# JKW_standalone.net
KiCad netlist of a schematic drawn in EAGLE
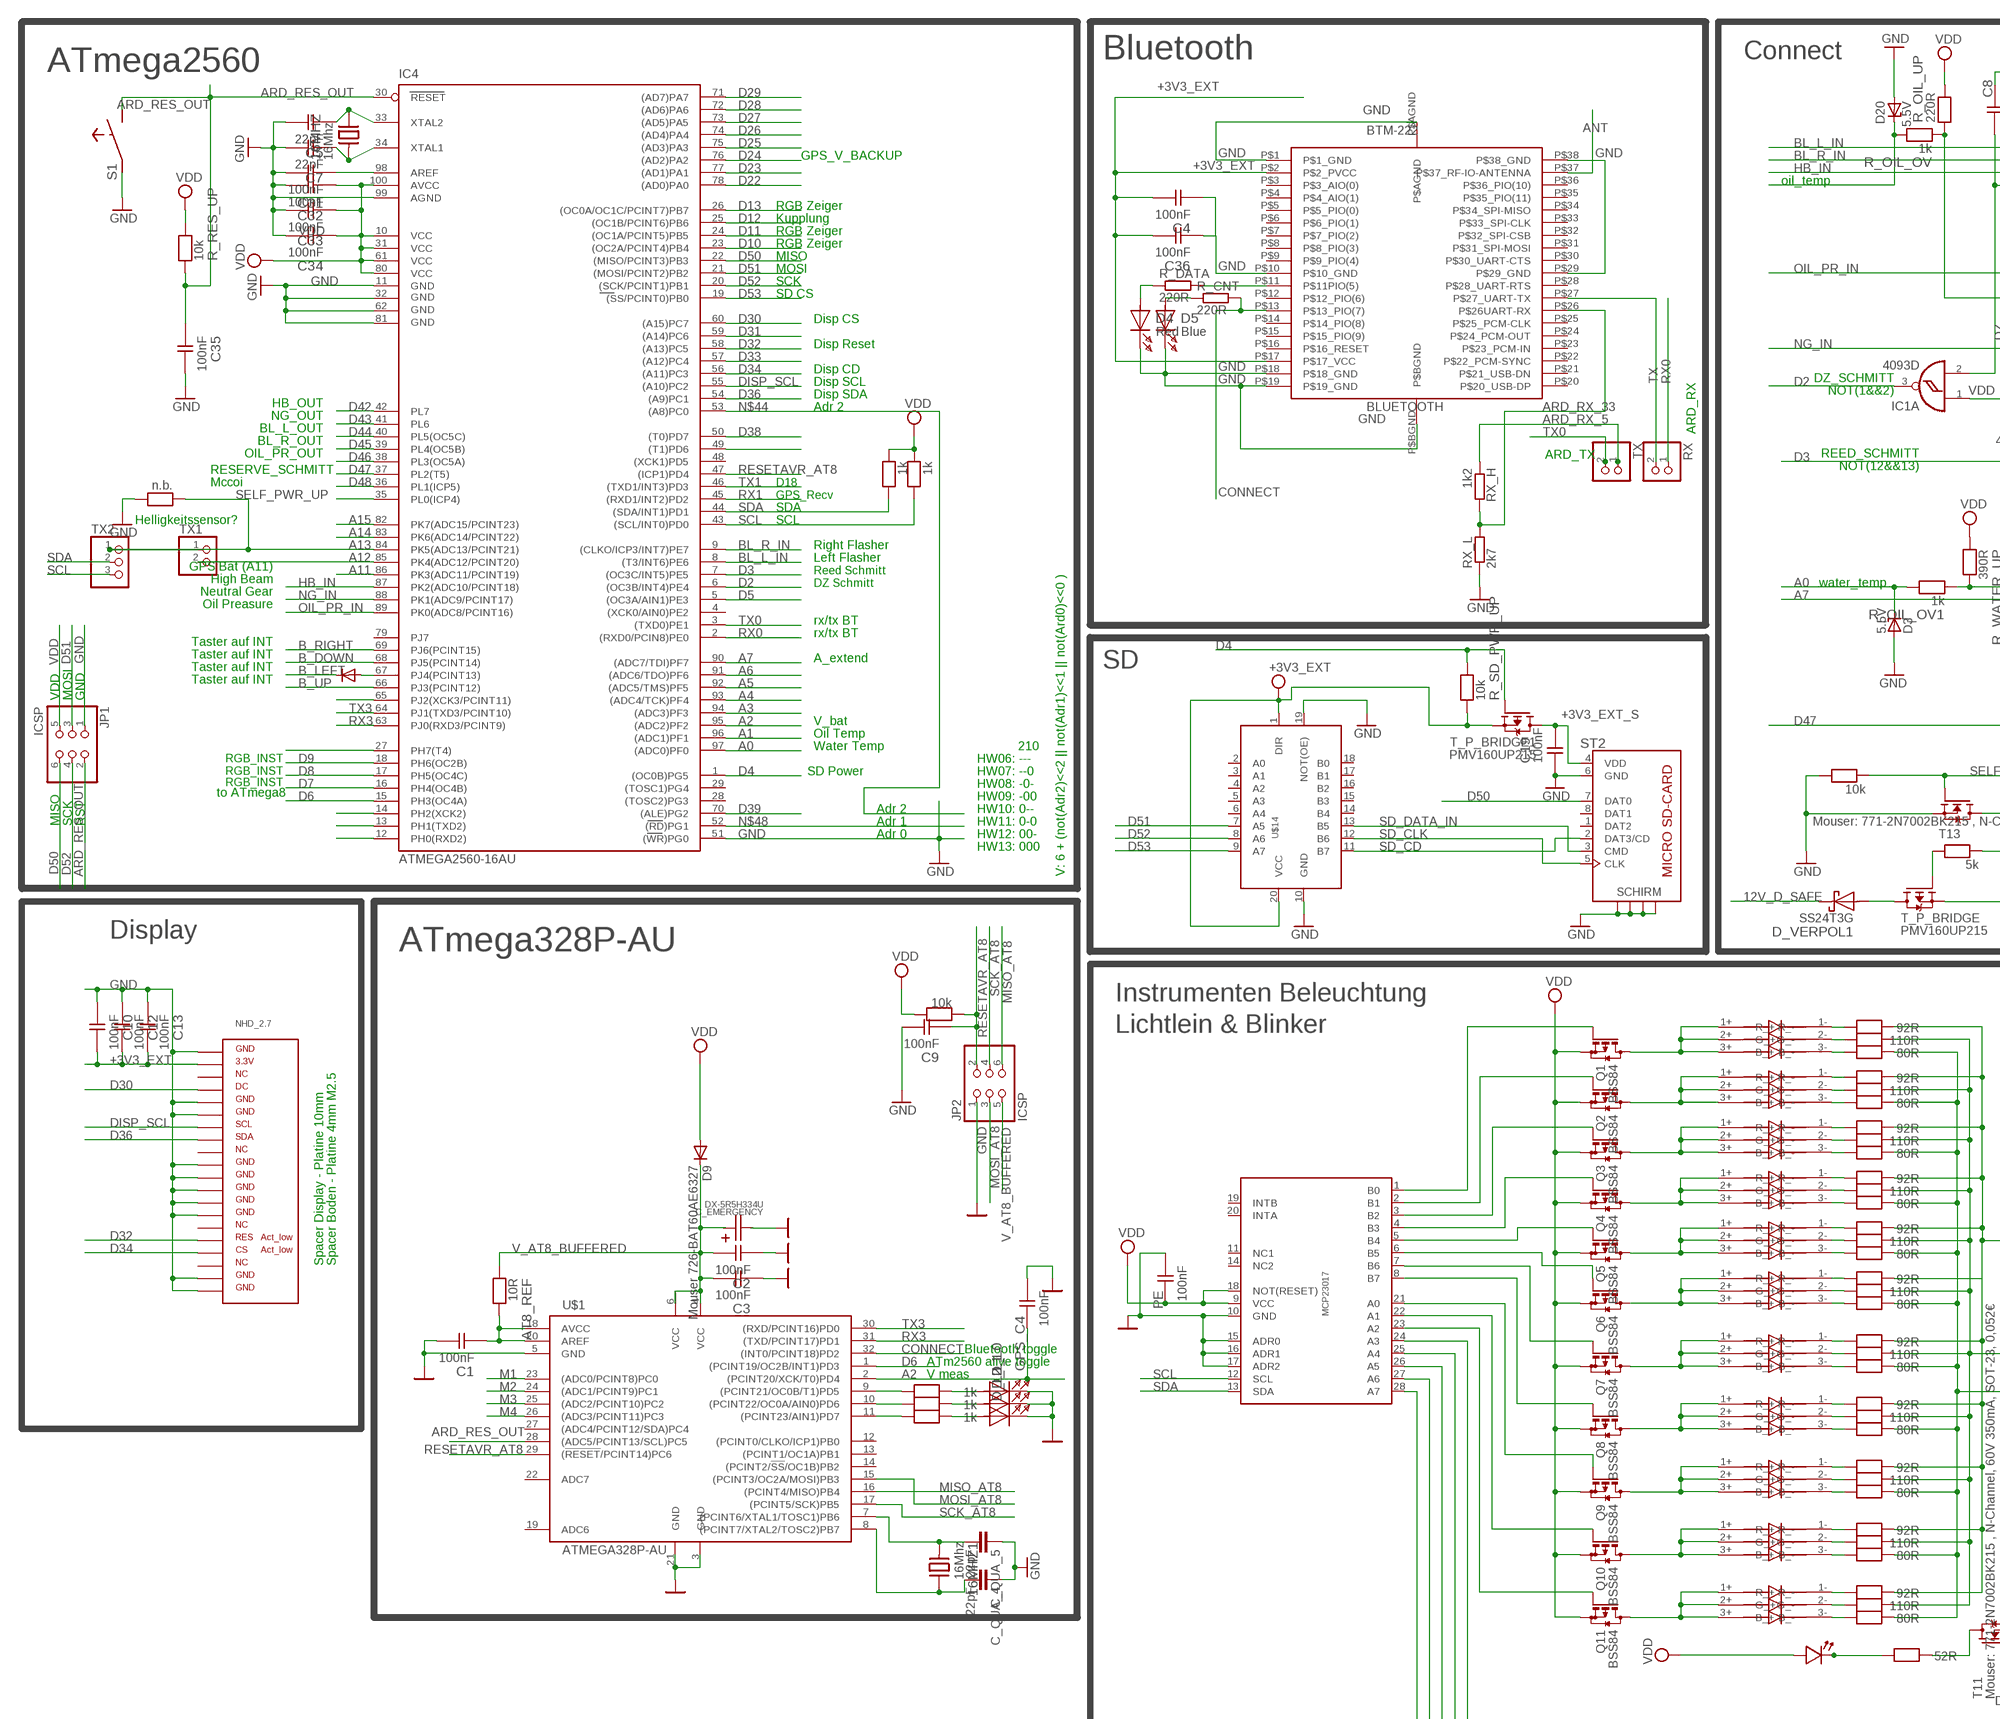
[diagram p0: schematic, sheet 1, part 1 of 3]
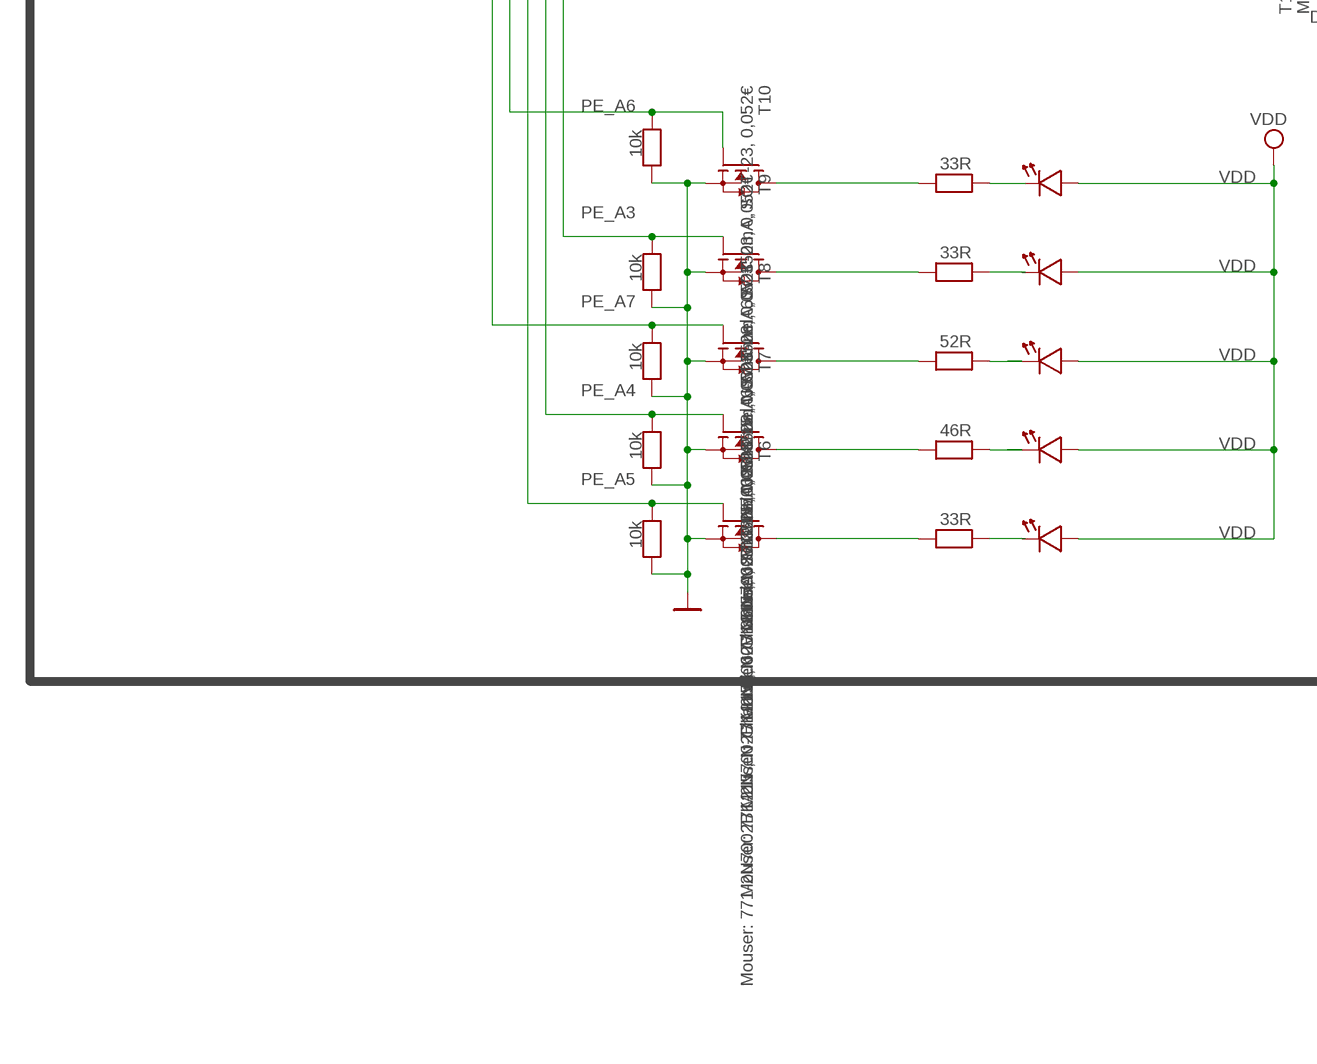
[diagram p1: schematic, sheet 1, part 2 of 3]
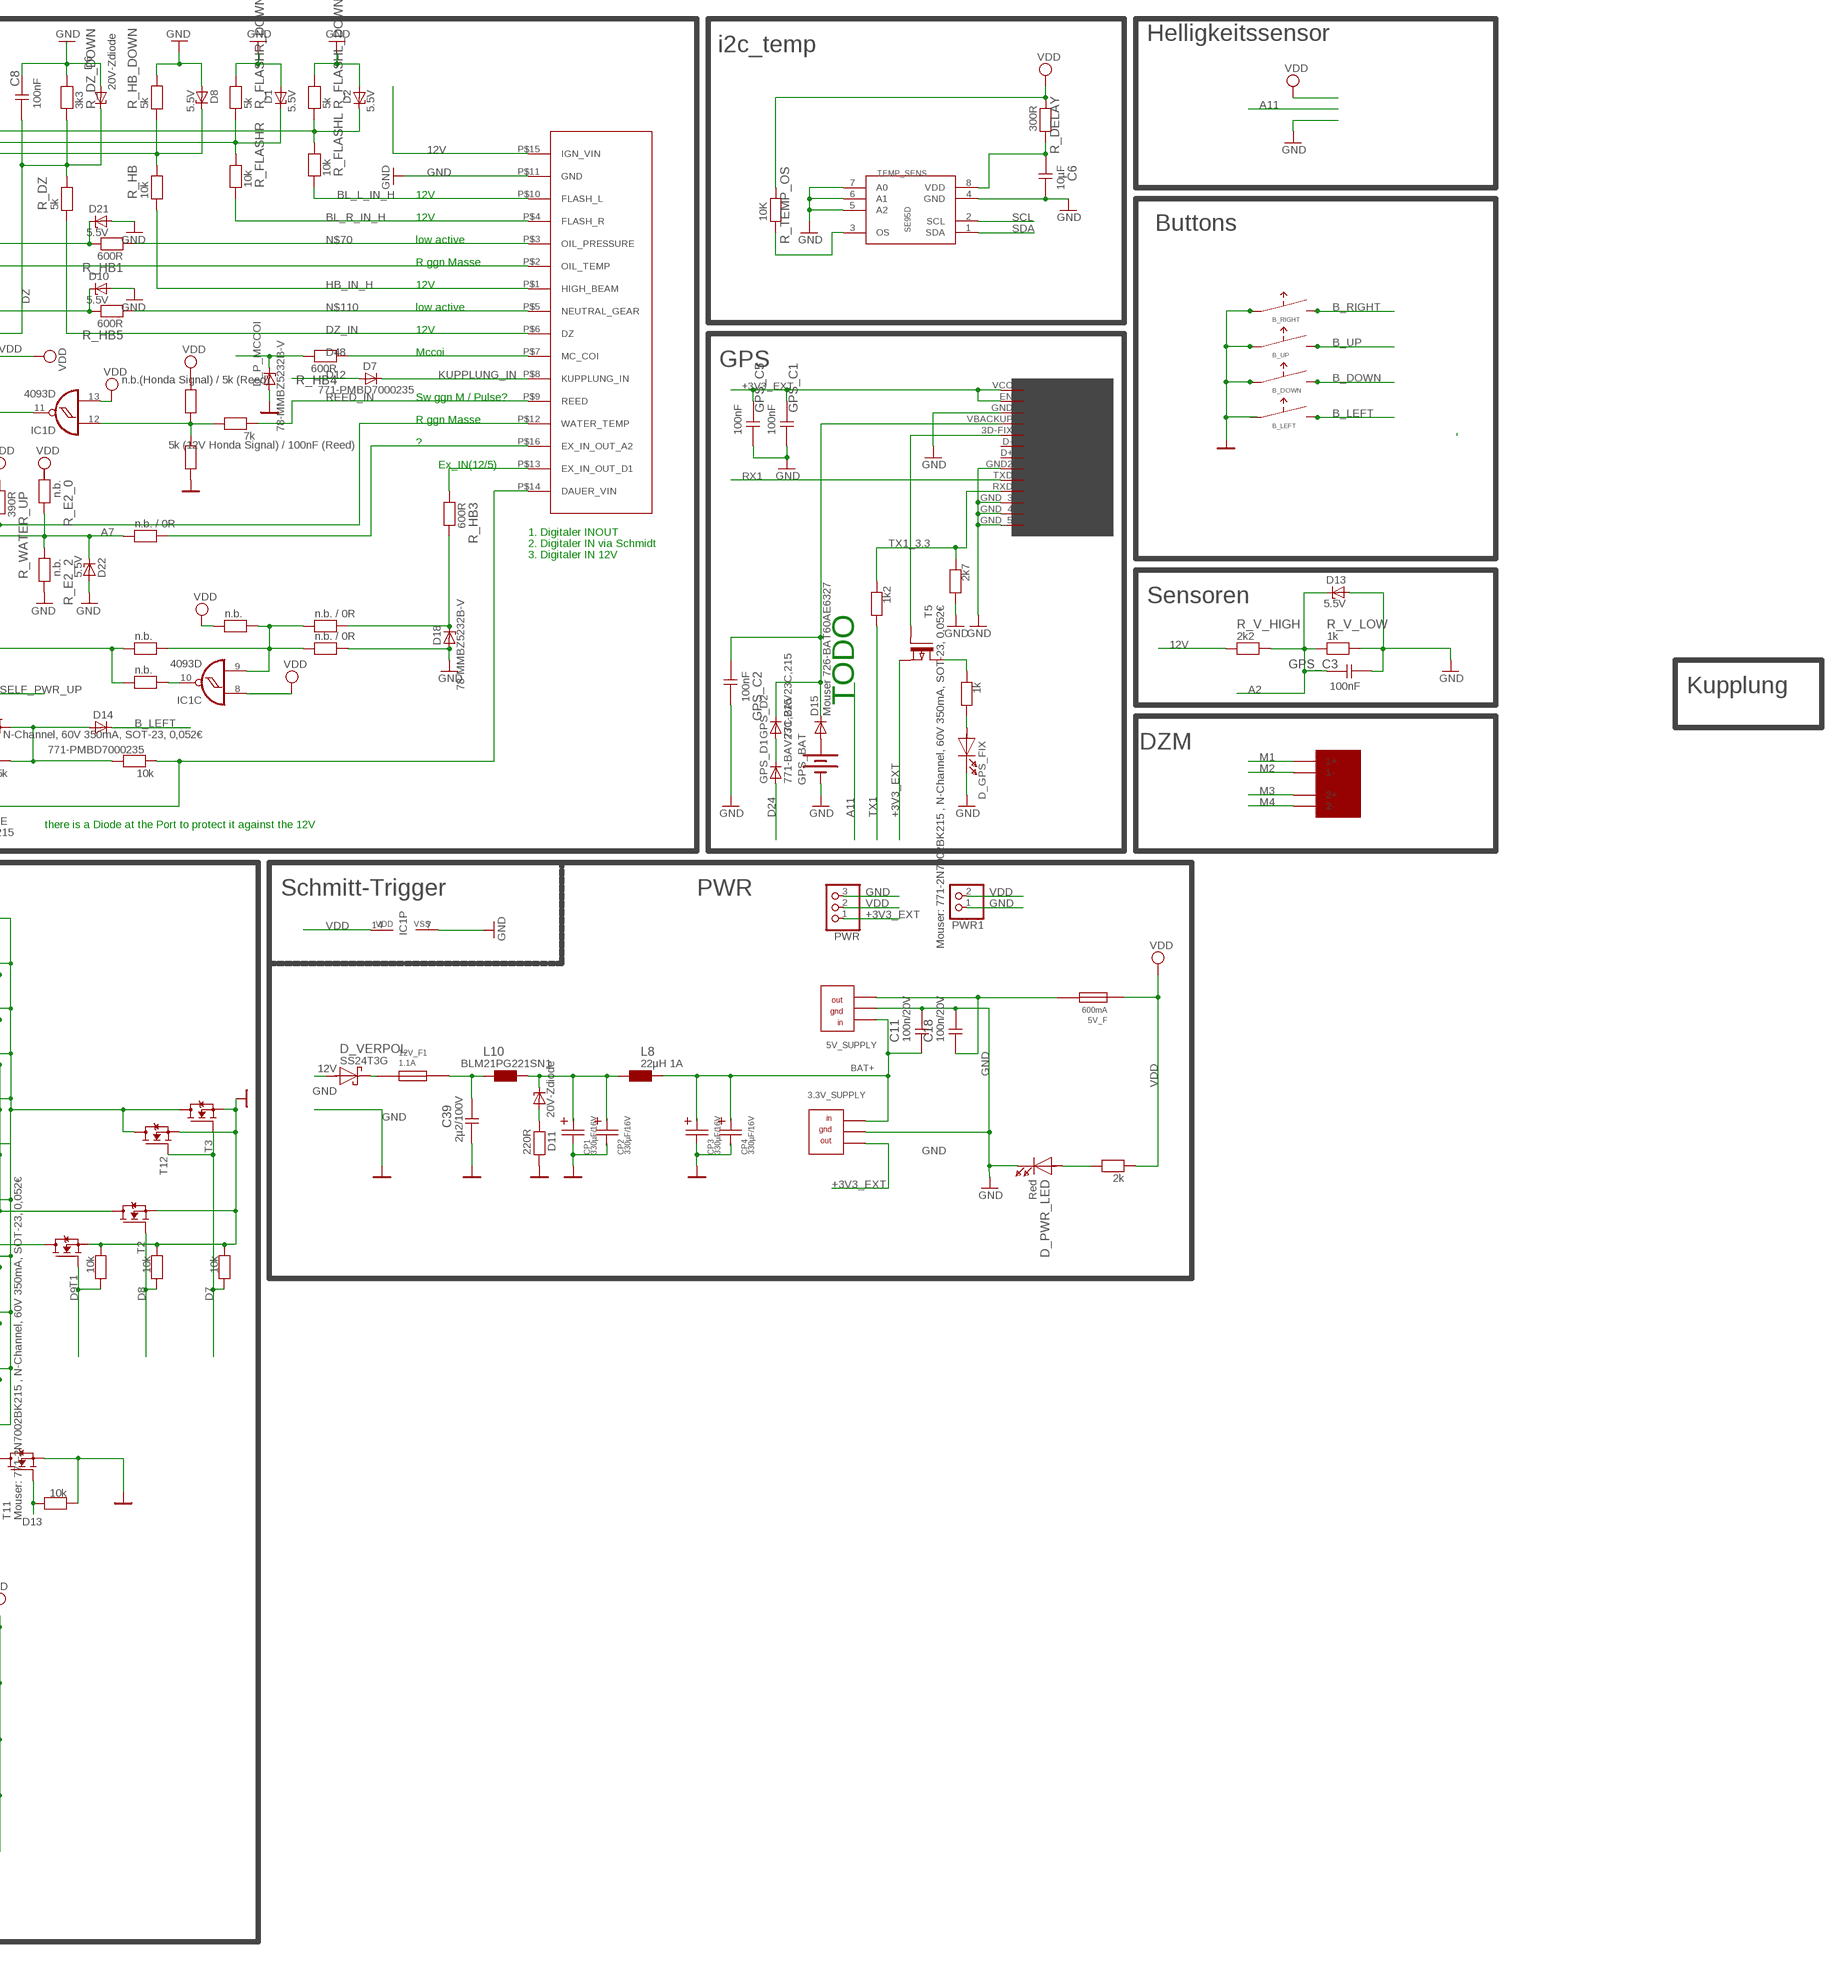
[diagram p2: schematic, sheet 1, part 3 of 3]

(export (version "E")
  (design (tool "Eeschema 10.0.6"))
  (components
    (comp (ref "3.3V_SUPPLY")
      (value "OKI78SR3.31.5WHC")
      (footprint "eagle-import:OKI-78SR")
      (libsource (lib "eagle-import") (part "OKI-78SR"))
    )
    (comp (ref "5V_F")
      (value "600mA")
      (footprint "eagle-import:POLY_FUSE")
      (libsource (lib "eagle-import") (part "POLY_FUSE"))
    )
    (comp (ref "5V_SUPPLY")
      (value "OKI78SR51.5W36HC")
      (footprint "eagle-import:OKI-78SR")
      (libsource (lib "eagle-import") (part "OKI-78SR"))
    )
    (comp (ref "12V_F1")
      (value "1.1A")
      (footprint "eagle-import:POLY_FUSE")
      (libsource (lib "eagle-import") (part "POLY_FUSE"))
    )
    (comp (ref "16MHZ")
      (value "16Mhz")
      (footprint "eagle-import:XT-HC49S-SMD")
      (libsource (lib "eagle-import") (part "XT-HC49-SMD"))
    )
    (comp (ref "16MHZ1")
      (value "16Mhz")
      (footprint "eagle-import:XT-HC49S-SMD")
      (libsource (lib "eagle-import") (part "XT-HC49-SMD"))
    )
    (comp (ref "AT8_REF")
      (value "10R")
      (footprint "eagle-import:0805")
      (libsource (lib "eagle-import") (part "R0805"))
    )
    (comp (ref "BLUETOOTH")
      (value "BTM-222")
      (footprint "eagle-import:BTM-222")
      (libsource (lib "eagle-import") (part "BTM-222"))
    )
    (comp (ref "B_DOWN")
      (value "SMD_TASTER_MIT_KAPPE")
      (footprint "eagle-import:SMD_DRUCKTASTER")
      (libsource (lib "eagle-import") (part "SMD_TASTER_MIT_KAPPE"))
    )
    (comp (ref "B_LEFT")
      (value "SMD_TASTER_MIT_KAPPE")
      (footprint "eagle-import:SMD_DRUCKTASTER")
      (libsource (lib "eagle-import") (part "SMD_TASTER_MIT_KAPPE"))
    )
    (comp (ref "B_RIGHT")
      (value "SMD_TASTER_MIT_KAPPE")
      (footprint "eagle-import:SMD_DRUCKTASTER")
      (libsource (lib "eagle-import") (part "SMD_TASTER_MIT_KAPPE"))
    )
    (comp (ref "B_UP")
      (value "SMD_TASTER_MIT_KAPPE")
      (footprint "eagle-import:SMD_DRUCKTASTER")
      (libsource (lib "eagle-import") (part "SMD_TASTER_MIT_KAPPE"))
    )
    (comp (ref "C1")
      (value "100nF")
      (footprint "eagle-import:0805")
      (libsource (lib "eagle-import") (part "C0805"))
    )
    (comp (ref "C2")
      (value "100nF")
      (footprint "eagle-import:0805")
      (libsource (lib "eagle-import") (part "C0805"))
    )
    (comp (ref "C3")
      (value "100nF")
      (footprint "eagle-import:0805")
      (libsource (lib "eagle-import") (part "C0805"))
    )
    (comp (ref "C4")
      (value "100nF")
      (footprint "eagle-import:0805")
      (libsource (lib "eagle-import") (part "C0805"))
    )
    (comp (ref "C5")
      (value "22pF")
      (footprint "eagle-import:0805")
      (libsource (lib "eagle-import") (part "C0805"))
    )
    (comp (ref "C6")
      (value "10µF")
      (footprint "eagle-import:0805")
      (libsource (lib "eagle-import") (part "C0805"))
    )
    (comp (ref "C7")
      (value "22pF")
      (footprint "eagle-import:0805")
      (libsource (lib "eagle-import") (part "C0805"))
    )
    (comp (ref "C8")
      (value "100nF")
      (footprint "eagle-import:0805")
      (libsource (lib "eagle-import") (part "C0805"))
    )
    (comp (ref "C9")
      (value "100nF")
      (footprint "eagle-import:0805")
      (libsource (lib "eagle-import") (part "C0805"))
    )
    (comp (ref "C10")
      (value "100nF")
      (footprint "eagle-import:0805")
      (libsource (lib "eagle-import") (part "C0805"))
    )
    (comp (ref "C11")
      (value "100n/20V")
      (footprint "eagle-import:0805")
      (libsource (lib "eagle-import") (part "C0805"))
    )
    (comp (ref "C12")
      (value "100nF")
      (footprint "eagle-import:0805")
      (libsource (lib "eagle-import") (part "C0805"))
    )
    (comp (ref "C13")
      (value "100nF")
      (footprint "eagle-import:0805")
      (libsource (lib "eagle-import") (part "C0805"))
    )
    (comp (ref "C18")
      (value "100n/20V")
      (footprint "eagle-import:0805")
      (libsource (lib "eagle-import") (part "C0805"))
    )
    (comp (ref "C19")
      (value "100nF")
      (footprint "eagle-import:0805")
      (libsource (lib "eagle-import") (part "C0805"))
    )
    (comp (ref "C31")
      (value "100nF")
      (footprint "eagle-import:0805")
      (libsource (lib "eagle-import") (part "C0805"))
    )
    (comp (ref "C32")
      (value "100nF")
      (footprint "eagle-import:0805")
      (libsource (lib "eagle-import") (part "C0805"))
    )
    (comp (ref "C33")
      (value "100nF")
      (footprint "eagle-import:0805")
      (libsource (lib "eagle-import") (part "C0805"))
    )
    (comp (ref "C34")
      (value "100nF")
      (footprint "eagle-import:0805")
      (libsource (lib "eagle-import") (part "C0805"))
    )
    (comp (ref "C35")
      (value "100nF")
      (footprint "eagle-import:0805")
      (libsource (lib "eagle-import") (part "C0805"))
    )
    (comp (ref "C36")
      (value "100nF")
      (footprint "eagle-import:0805")
      (libsource (lib "eagle-import") (part "C0805"))
    )
    (comp (ref "C39")
      (value "2µ2/100V")
      (footprint "eagle-import:0805")
      (libsource (lib "eagle-import") (part "C0805"))
    )
    (comp (ref "CP1")
      (value "330µF/16V")
      (footprint "eagle-import:SMD_SMT_6.6_6.6")
      (libsource (lib "eagle-import") (part "C_SMD_SMP"))
    )
    (comp (ref "CP2")
      (value "330µF/16V")
      (footprint "eagle-import:SMD_SMT_6.6_6.6")
      (libsource (lib "eagle-import") (part "C_SMD_SMP"))
    )
    (comp (ref "CP3")
      (value "330µF/16V")
      (footprint "eagle-import:SMD_SMT_6.6_6.6")
      (libsource (lib "eagle-import") (part "C_SMD_SMP"))
    )
    (comp (ref "CP4")
      (value "330µF/16V")
      (footprint "eagle-import:SMD_SMT_6.6_6.6")
      (libsource (lib "eagle-import") (part "C_SMD_SMP"))
    )
    (comp (ref "C_EMERGENCY")
      (value "DX-5R5H334U")
      (footprint "eagle-import:GOLDCAP")
      (libsource (lib "eagle-import") (part "DX-5R5H334U"))
    )
    (comp (ref "C_QUA_4")
      (value "22pF")
      (footprint "eagle-import:C0805")
      (libsource (lib "eagle-import") (part "C-EUC0805"))
    )
    (comp (ref "C_QUA_5")
      (value "22pF")
      (footprint "eagle-import:C0805")
      (libsource (lib "eagle-import") (part "C-EUC0805"))
    )
    (comp (ref "D1")
      (value "5.5V")
      (footprint "eagle-import:SOT23")
      (libsource (lib "eagle-import") (part "ZENER-DIODESOT23"))
    )
    (comp (ref "D2")
      (value "5.5V")
      (footprint "eagle-import:SOT23")
      (libsource (lib "eagle-import") (part "ZENER-DIODESOT23"))
    )
    (comp (ref "D3")
      (value "5.5V")
      (footprint "eagle-import:SOT23")
      (libsource (lib "eagle-import") (part "ZENER-DIODESOT23"))
    )
    (comp (ref "D4")
      (value "Red")
      (footprint "eagle-import:LED-0805")
      (libsource (lib "eagle-import") (part "LED0805"))
    )
    (comp (ref "D5")
      (value "Blue")
      (footprint "eagle-import:LED-0805")
      (libsource (lib "eagle-import") (part "LED0805"))
    )
    (comp (ref "D6")
      (value "20V-Zdiode")
      (footprint "eagle-import:SOT23")
      (libsource (lib "eagle-import") (part "ZENER-DIODESOT23"))
    )
    (comp (ref "D7")
      (value "771-PMBD7000235")
      (footprint "eagle-import:SOT23")
      (libsource (lib "eagle-import") (part "D-A1-C3"))
    )
    (comp (ref "D8")
      (value "5.5V")
      (footprint "eagle-import:SOT23")
      (libsource (lib "eagle-import") (part "ZENER-DIODESOT23"))
    )
    (comp (ref "D9")
      (value "Mouser 726-BAT60AE6327")
      (footprint "eagle-import:SOD323-W")
      (libsource (lib "eagle-import") (part "DIODE-SOD323-W"))
    )
    (comp (ref "D10")
      (value "5.5V")
      (footprint "eagle-import:SOT23")
      (libsource (lib "eagle-import") (part "ZENER-DIODESOT23"))
    )
    (comp (ref "D11")
      (value "20V-Zdiode")
      (footprint "eagle-import:SOT23")
      (libsource (lib "eagle-import") (part "ZENER-DIODESOT23"))
    )
    (comp (ref "D12")
      (value "771-PMBD7000235")
      (footprint "eagle-import:SOT23")
      (libsource (lib "eagle-import") (part "D-A1-C3"))
    )
    (comp (ref "D13")
      (value "5.5V")
      (footprint "eagle-import:SOT23")
      (libsource (lib "eagle-import") (part "ZENER-DIODESOT23"))
    )
    (comp (ref "D14")
      (value "771-PMBD7000235")
      (footprint "eagle-import:SOT23")
      (libsource (lib "eagle-import") (part "D-A1-C3"))
    )
    (comp (ref "D15")
      (value "Mouser 726-BAT60AE6327")
      (footprint "eagle-import:SOD323-W")
      (libsource (lib "eagle-import") (part "DIODE-SOD323-W"))
    )
    (comp (ref "D18")
      (value "78-MMBZ5232B-V")
      (footprint "eagle-import:SOT23")
      (libsource (lib "eagle-import") (part "ZENER-DIODESOT23"))
    )
    (comp (ref "D20")
      (value "5.5V")
      (footprint "eagle-import:SOT23")
      (libsource (lib "eagle-import") (part "ZENER-DIODESOT23"))
    )
    (comp (ref "D21")
      (value "5.5V")
      (footprint "eagle-import:SOT23")
      (libsource (lib "eagle-import") (part "ZENER-DIODESOT23"))
    )
    (comp (ref "D22")
      (value "5.5V")
      (footprint "eagle-import:SOT23")
      (libsource (lib "eagle-import") (part "ZENER-DIODESOT23"))
    )
    (comp (ref "D_GPS_FIX")
      (value "Red")
      (footprint "eagle-import:LED-0805")
      (libsource (lib "eagle-import") (part "LED0805"))
    )
    (comp (ref "D_GR_BLR")
      (value "PLCC4_LED")
      (footprint "eagle-import:PLCC-4")
      (libsource (lib "eagle-import") (part "PLCC4_LED"))
    )
    (comp (ref "D_GR_N")
      (value "PLCC4_LED")
      (footprint "eagle-import:PLCC-4")
      (libsource (lib "eagle-import") (part "PLCC4_LED"))
    )
    (comp (ref "D_L0")
      (value "LED0805")
      (footprint "eagle-import:LED-0805")
      (libsource (lib "eagle-import") (part "LED0805"))
    )
    (comp (ref "D_L1")
      (value "LED0805")
      (footprint "eagle-import:LED-0805")
      (libsource (lib "eagle-import") (part "LED0805"))
    )
    (comp (ref "D_L2")
      (value "LED0805")
      (footprint "eagle-import:LED-0805")
      (libsource (lib "eagle-import") (part "LED0805"))
    )
    (comp (ref "D_PWR_LED")
      (value "Red")
      (footprint "eagle-import:LED-0805")
      (libsource (lib "eagle-import") (part "LED0805"))
    )
    (comp (ref "D_P_MCCOI")
      (value "78-MMBZ5232B-V")
      (footprint "eagle-import:SOT23")
      (libsource (lib "eagle-import") (part "ZENER-DIODESOT23"))
    )
    (comp (ref "D_VERPOL")
      (value "SS24T3G")
      (footprint "eagle-import:SMB")
      (libsource (lib "eagle-import") (part "D-SSMB-A+K"))
    )
    (comp (ref "D_VERPOL1")
      (value "SS24T3G")
      (footprint "eagle-import:SMB")
      (libsource (lib "eagle-import") (part "D-SSMB-A+K"))
    )
    (comp (ref "GPS")
      (value "MT3329")
      (footprint "eagle-import:MT3329")
      (libsource (lib "eagle-import") (part "MT3329"))
    )
    (comp (ref "GPS_BAT")
      (value "F_908642")
      (footprint "eagle-import:BATTCON_12MM")
      (libsource (lib "eagle-import") (part "BATTERY12MM"))
    )
    (comp (ref "GPS_C1")
      (value "100nF")
      (footprint "eagle-import:0805")
      (libsource (lib "eagle-import") (part "C0805"))
    )
    (comp (ref "GPS_C2")
      (value "100nF")
      (footprint "eagle-import:0805")
      (libsource (lib "eagle-import") (part "C0805"))
    )
    (comp (ref "GPS_C3")
      (value "100nF")
      (footprint "eagle-import:0805")
      (libsource (lib "eagle-import") (part "C0805"))
    )
    (comp (ref "GPS_C4")
      (value "100nF")
      (footprint "eagle-import:0805")
      (libsource (lib "eagle-import") (part "C0805"))
    )
    (comp (ref "GPS_C5")
      (value "100nF")
      (footprint "eagle-import:0805")
      (libsource (lib "eagle-import") (part "C0805"))
    )
    (comp (ref "GPS_D1")
      (value "771-BAV23C,215")
      (footprint "eagle-import:SOT23")
      (libsource (lib "eagle-import") (part "D-A1-C3"))
    )
    (comp (ref "GPS_D2")
      (value "771-BAV23C,215")
      (footprint "eagle-import:SOT23")
      (libsource (lib "eagle-import") (part "D-A1-C3"))
    )
    (comp (ref "IC1")
      (value "4093D")
      (footprint "eagle-import:SO14")
      (libsource (lib "eagle-import") (part "4093D"))
    )
    (comp (ref "IC4")
      (value "ATMEGA2560-16AU")
      (footprint "eagle-import:TQFP100")
      (libsource (lib "eagle-import") (part "ATMEGAAU2560-16"))
    )
    (comp (ref "JP1")
      (value "ICSP")
      (footprint "eagle-import:2X03")
      (libsource (lib "eagle-import") (part "PINHD-2X3"))
    )
    (comp (ref "JP2")
      (value "ICSP")
      (footprint "eagle-import:2X03")
      (libsource (lib "eagle-import") (part "PINHD-2X3"))
    )
    (comp (ref "L8")
      (value "22µH 1A")
      (footprint "eagle-import:L-PD54")
      (libsource (lib "eagle-import") (part "LPD54"))
    )
    (comp (ref "L10")
      (value "BLM21PG221SN1")
      (footprint "eagle-import:0805+603")
      (libsource (lib "eagle-import") (part "L0808+0603"))
    )
    (comp (ref "NHD_2.7")
      (value "NHD_2.7_SOLO_RO")
      (footprint "eagle-import:NHD_2.7_SOLO_RO")
      (libsource (lib "eagle-import") (part "NHD_2.7_SOLO_RO"))
    )
    (comp (ref "PE")
      (value "100nF")
      (footprint "eagle-import:0805")
      (libsource (lib "eagle-import") (part "C0805"))
    )
    (comp (ref "PWR")
      (value "PINHD-1X3")
      (footprint "eagle-import:1X03")
      (libsource (lib "eagle-import") (part "PINHD-1X3"))
    )
    (comp (ref "PWR1")
      (value "PINHD-1X2")
      (footprint "eagle-import:1X02")
      (libsource (lib "eagle-import") (part "PINHD-1X2"))
    )
    (comp (ref "Q1")
      (value "BSS84")
      (footprint "eagle-import:SOT23")
      (libsource (lib "eagle-import") (part "BSS84"))
    )
    (comp (ref "Q2")
      (value "BSS84")
      (footprint "eagle-import:SOT23")
      (libsource (lib "eagle-import") (part "BSS84"))
    )
    (comp (ref "Q3")
      (value "BSS84")
      (footprint "eagle-import:SOT23")
      (libsource (lib "eagle-import") (part "BSS84"))
    )
    (comp (ref "Q4")
      (value "BSS84")
      (footprint "eagle-import:SOT23")
      (libsource (lib "eagle-import") (part "BSS84"))
    )
    (comp (ref "Q5")
      (value "BSS84")
      (footprint "eagle-import:SOT23")
      (libsource (lib "eagle-import") (part "BSS84"))
    )
    (comp (ref "Q6")
      (value "BSS84")
      (footprint "eagle-import:SOT23")
      (libsource (lib "eagle-import") (part "BSS84"))
    )
    (comp (ref "Q7")
      (value "BSS84")
      (footprint "eagle-import:SOT23")
      (libsource (lib "eagle-import") (part "BSS84"))
    )
    (comp (ref "Q8")
      (value "BSS84")
      (footprint "eagle-import:SOT23")
      (libsource (lib "eagle-import") (part "BSS84"))
    )
    (comp (ref "Q9")
      (value "BSS84")
      (footprint "eagle-import:SOT23")
      (libsource (lib "eagle-import") (part "BSS84"))
    )
    (comp (ref "Q10")
      (value "BSS84")
      (footprint "eagle-import:SOT23")
      (libsource (lib "eagle-import") (part "BSS84"))
    )
    (comp (ref "Q11")
      (value "BSS84")
      (footprint "eagle-import:SOT23")
      (libsource (lib "eagle-import") (part "BSS84"))
    )
    (comp (ref "RGB_1")
      (value "RGB_LED")
      (footprint "eagle-import:PLCC-6")
      (libsource (lib "eagle-import") (part "RGB_LED"))
    )
    (comp (ref "RGB_2")
      (value "RGB_LED")
      (footprint "eagle-import:PLCC-6")
      (libsource (lib "eagle-import") (part "RGB_LED"))
    )
    (comp (ref "RGB_3")
      (value "RGB_LED")
      (footprint "eagle-import:PLCC-6")
      (libsource (lib "eagle-import") (part "RGB_LED"))
    )
    (comp (ref "RGB_4")
      (value "RGB_LED")
      (footprint "eagle-import:PLCC-6")
      (libsource (lib "eagle-import") (part "RGB_LED"))
    )
    (comp (ref "RGB_5")
      (value "RGB_LED")
      (footprint "eagle-import:PLCC-6")
      (libsource (lib "eagle-import") (part "RGB_LED"))
    )
    (comp (ref "RGB_6")
      (value "RGB_LED")
      (footprint "eagle-import:PLCC-6")
      (libsource (lib "eagle-import") (part "RGB_LED"))
    )
    (comp (ref "RGB_7")
      (value "RGB_LED")
      (footprint "eagle-import:PLCC-6")
      (libsource (lib "eagle-import") (part "RGB_LED"))
    )
    (comp (ref "RGB_8")
      (value "RGB_LED")
      (footprint "eagle-import:PLCC-6")
      (libsource (lib "eagle-import") (part "RGB_LED"))
    )
    (comp (ref "RGB_9")
      (value "RGB_LED")
      (footprint "eagle-import:PLCC-6")
      (libsource (lib "eagle-import") (part "RGB_LED"))
    )
    (comp (ref "RGB_10")
      (value "RGB_LED")
      (footprint "eagle-import:PLCC-6")
      (libsource (lib "eagle-import") (part "RGB_LED"))
    )
    (comp (ref "RGB_11")
      (value "RGB_LED")
      (footprint "eagle-import:PLCC-6")
      (libsource (lib "eagle-import") (part "RGB_LED"))
    )
    (comp (ref "RX")
      (value "PINHD-1X2")
      (footprint "eagle-import:1X02")
      (libsource (lib "eagle-import") (part "PINHD-1X2"))
    )
    (comp (ref "RX_H")
      (value "1k2")
      (footprint "eagle-import:M0805")
      (libsource (lib "eagle-import") (part "resistor_R-EU_M0805"))
    )
    (comp (ref "RX_L")
      (value "2k7")
      (footprint "eagle-import:M0805")
      (libsource (lib "eagle-import") (part "resistor_R-EU_M0805"))
    )
    (comp (ref "R_BL_L")
      (value "33R")
      (footprint "eagle-import:0805")
      (libsource (lib "eagle-import") (part "R0805"))
    )
    (comp (ref "R_BL_L1")
      (value "n.b.")
      (footprint "eagle-import:0805")
      (libsource (lib "eagle-import") (part "R0805"))
    )
    (comp (ref "R_BL_R")
      (value "33R")
      (footprint "eagle-import:0805")
      (libsource (lib "eagle-import") (part "R0805"))
    )
    (comp (ref "R_B_LED_1")
      (value "80R")
      (footprint "eagle-import:0805")
      (libsource (lib "eagle-import") (part "R0805"))
    )
    (comp (ref "R_B_LED_2")
      (value "80R")
      (footprint "eagle-import:0805")
      (libsource (lib "eagle-import") (part "R0805"))
    )
    (comp (ref "R_B_LED_3")
      (value "80R")
      (footprint "eagle-import:0805")
      (libsource (lib "eagle-import") (part "R0805"))
    )
    (comp (ref "R_B_LED_4")
      (value "80R")
      (footprint "eagle-import:0805")
      (libsource (lib "eagle-import") (part "R0805"))
    )
    (comp (ref "R_B_LED_5")
      (value "80R")
      (footprint "eagle-import:0805")
      (libsource (lib "eagle-import") (part "R0805"))
    )
    (comp (ref "R_B_LED_6")
      (value "80R")
      (footprint "eagle-import:0805")
      (libsource (lib "eagle-import") (part "R0805"))
    )
    (comp (ref "R_B_LED_7")
      (value "80R")
      (footprint "eagle-import:0805")
      (libsource (lib "eagle-import") (part "R0805"))
    )
    (comp (ref "R_B_LED_8")
      (value "80R")
      (footprint "eagle-import:0805")
      (libsource (lib "eagle-import") (part "R0805"))
    )
    (comp (ref "R_B_LED_9")
      (value "80R")
      (footprint "eagle-import:0805")
      (libsource (lib "eagle-import") (part "R0805"))
    )
    (comp (ref "R_B_LED_10")
      (value "80R")
      (footprint "eagle-import:0805")
      (libsource (lib "eagle-import") (part "R0805"))
    )
    (comp (ref "R_B_LED_11")
      (value "80R")
      (footprint "eagle-import:0805")
      (libsource (lib "eagle-import") (part "R0805"))
    )
    (comp (ref "R_B_LED_12")
      (value "10k")
      (footprint "eagle-import:0805")
      (libsource (lib "eagle-import") (part "R0805"))
    )
    (comp (ref "R_B_LED_13")
      (value "10k")
      (footprint "eagle-import:0805")
      (libsource (lib "eagle-import") (part "R0805"))
    )
    (comp (ref "R_B_LED_14")
      (value "10k")
      (footprint "eagle-import:0805")
      (libsource (lib "eagle-import") (part "R0805"))
    )
    (comp (ref "R_B_LED_15")
      (value "10k")
      (footprint "eagle-import:0805")
      (libsource (lib "eagle-import") (part "R0805"))
    )
    (comp (ref "R_B_LED_16")
      (value "10k")
      (footprint "eagle-import:0805")
      (libsource (lib "eagle-import") (part "R0805"))
    )
    (comp (ref "R_B_LED_17")
      (value "10k")
      (footprint "eagle-import:0805")
      (libsource (lib "eagle-import") (part "R0805"))
    )
    (comp (ref "R_B_LED_18")
      (value "10k")
      (footprint "eagle-import:0805")
      (libsource (lib "eagle-import") (part "R0805"))
    )
    (comp (ref "R_B_LED_19")
      (value "10k")
      (footprint "eagle-import:0805")
      (libsource (lib "eagle-import") (part "R0805"))
    )
    (comp (ref "R_B_LED_20")
      (value "10k")
      (footprint "eagle-import:0805")
      (libsource (lib "eagle-import") (part "R0805"))
    )
    (comp (ref "R_CNT")
      (value "220R")
      (footprint "eagle-import:M0805")
      (libsource (lib "eagle-import") (part "R-EU_M0805"))
    )
    (comp (ref "R_DATA")
      (value "220R")
      (footprint "eagle-import:M0805")
      (libsource (lib "eagle-import") (part "R-EU_M0805"))
    )
    (comp (ref "R_DEAKT_DAUER_P")
      (value "10k")
      (footprint "eagle-import:0805")
      (libsource (lib "eagle-import") (part "R0805"))
    )
    (comp (ref "R_DEAKT_DAUER_P1")
      (value "10k")
      (footprint "eagle-import:0805")
      (libsource (lib "eagle-import") (part "R0805"))
    )
    (comp (ref "R_DEAKT_DAUER_P2")
      (value "5k")
      (footprint "eagle-import:0805")
      (libsource (lib "eagle-import") (part "R0805"))
    )
    (comp (ref "R_DELAY")
      (value "300R")
      (footprint "eagle-import:0805")
      (libsource (lib "eagle-import") (part "R0805"))
    )
    (comp (ref "R_DZ")
      (value "5k")
      (footprint "eagle-import:0805")
      (libsource (lib "eagle-import") (part "R0805"))
    )
    (comp (ref "R_DZ_DOWN")
      (value "3k3")
      (footprint "eagle-import:0805")
      (libsource (lib "eagle-import") (part "R0805"))
    )
    (comp (ref "R_E1_0")
      (value "n.b.")
      (footprint "eagle-import:0805")
      (libsource (lib "eagle-import") (part "R0805"))
    )
    (comp (ref "R_E1_1")
      (value "n.b. / 0R")
      (footprint "eagle-import:0805")
      (libsource (lib "eagle-import") (part "R0805"))
    )
    (comp (ref "R_E1_2")
      (value "n.b.")
      (footprint "eagle-import:0805")
      (libsource (lib "eagle-import") (part "R0805"))
    )
    (comp (ref "R_E1_3")
      (value "n.b. / 0R")
      (footprint "eagle-import:0805")
      (libsource (lib "eagle-import") (part "R0805"))
    )
    (comp (ref "R_E1_4")
      (value "n.b.")
      (footprint "eagle-import:0805")
      (libsource (lib "eagle-import") (part "R0805"))
    )
    (comp (ref "R_E2_0")
      (value "n.b.")
      (footprint "eagle-import:0805")
      (libsource (lib "eagle-import") (part "R0805"))
    )
    (comp (ref "R_E2_1")
      (value "n.b. / 0R")
      (footprint "eagle-import:0805")
      (libsource (lib "eagle-import") (part "R0805"))
    )
    (comp (ref "R_E2_2")
      (value "n.b.")
      (footprint "eagle-import:0805")
      (libsource (lib "eagle-import") (part "R0805"))
    )
    (comp (ref "R_FLASHL")
      (value "10k")
      (footprint "eagle-import:0805")
      (libsource (lib "eagle-import") (part "R0805"))
    )
    (comp (ref "R_FLASHL_DOWN")
      (value "5k")
      (footprint "eagle-import:0805")
      (libsource (lib "eagle-import") (part "R0805"))
    )
    (comp (ref "R_FLASHR")
      (value "10k")
      (footprint "eagle-import:0805")
      (libsource (lib "eagle-import") (part "R0805"))
    )
    (comp (ref "R_FLASHR_DOWN")
      (value "5k")
      (footprint "eagle-import:0805")
      (libsource (lib "eagle-import") (part "R0805"))
    )
    (comp (ref "R_GPS_LED")
      (value "1k")
      (footprint "eagle-import:0805")
      (libsource (lib "eagle-import") (part "R0805"))
    )
    (comp (ref "R_GR_BL_L")
      (value "PLCC4_LED")
      (footprint "eagle-import:PLCC-4")
      (libsource (lib "eagle-import") (part "PLCC4_LED"))
    )
    (comp (ref "R_G_LED_1")
      (value "110R")
      (footprint "eagle-import:0805")
      (libsource (lib "eagle-import") (part "R0805"))
    )
    (comp (ref "R_G_LED_2")
      (value "110R")
      (footprint "eagle-import:0805")
      (libsource (lib "eagle-import") (part "R0805"))
    )
    (comp (ref "R_G_LED_3")
      (value "110R")
      (footprint "eagle-import:0805")
      (libsource (lib "eagle-import") (part "R0805"))
    )
    (comp (ref "R_G_LED_4")
      (value "110R")
      (footprint "eagle-import:0805")
      (libsource (lib "eagle-import") (part "R0805"))
    )
    (comp (ref "R_G_LED_5")
      (value "110R")
      (footprint "eagle-import:0805")
      (libsource (lib "eagle-import") (part "R0805"))
    )
    (comp (ref "R_G_LED_6")
      (value "110R")
      (footprint "eagle-import:0805")
      (libsource (lib "eagle-import") (part "R0805"))
    )
    (comp (ref "R_G_LED_7")
      (value "110R")
      (footprint "eagle-import:0805")
      (libsource (lib "eagle-import") (part "R0805"))
    )
    (comp (ref "R_G_LED_8")
      (value "110R")
      (footprint "eagle-import:0805")
      (libsource (lib "eagle-import") (part "R0805"))
    )
    (comp (ref "R_G_LED_9")
      (value "110R")
      (footprint "eagle-import:0805")
      (libsource (lib "eagle-import") (part "R0805"))
    )
    (comp (ref "R_G_LED_10")
      (value "110R")
      (footprint "eagle-import:0805")
      (libsource (lib "eagle-import") (part "R0805"))
    )
    (comp (ref "R_G_LED_11")
      (value "110R")
      (footprint "eagle-import:0805")
      (libsource (lib "eagle-import") (part "R0805"))
    )
    (comp (ref "R_HB")
      (value "10k")
      (footprint "eagle-import:0805")
      (libsource (lib "eagle-import") (part "R0805"))
    )
    (comp (ref "R_HB1")
      (value "600R")
      (footprint "eagle-import:0805")
      (libsource (lib "eagle-import") (part "R0805"))
    )
    (comp (ref "R_HB3")
      (value "600R")
      (footprint "eagle-import:0805")
      (libsource (lib "eagle-import") (part "R0805"))
    )
    (comp (ref "R_HB4")
      (value "600R")
      (footprint "eagle-import:0805")
      (libsource (lib "eagle-import") (part "R0805"))
    )
    (comp (ref "R_HB5")
      (value "600R")
      (footprint "eagle-import:0805")
      (libsource (lib "eagle-import") (part "R0805"))
    )
    (comp (ref "R_HB_DOWN")
      (value "5k")
      (footprint "eagle-import:0805")
      (libsource (lib "eagle-import") (part "R0805"))
    )
    (comp (ref "R_HIGHB")
      (value "46R")
      (footprint "eagle-import:0805")
      (libsource (lib "eagle-import") (part "R0805"))
    )
    (comp (ref "R_L0")
      (value "1k")
      (footprint "eagle-import:0805")
      (libsource (lib "eagle-import") (part "R0805"))
    )
    (comp (ref "R_L1")
      (value "1k")
      (footprint "eagle-import:0805")
      (libsource (lib "eagle-import") (part "R0805"))
    )
    (comp (ref "R_L2")
      (value "1k")
      (footprint "eagle-import:0805")
      (libsource (lib "eagle-import") (part "R0805"))
    )
    (comp (ref "R_L3")
      (value "10k")
      (footprint "eagle-import:0805")
      (libsource (lib "eagle-import") (part "R0805"))
    )
    (comp (ref "R_LED_5V")
      (value "2k")
      (footprint "eagle-import:0805")
      (libsource (lib "eagle-import") (part "R0805"))
    )
    (comp (ref "R_N")
      (value "33R")
      (footprint "eagle-import:0805")
      (libsource (lib "eagle-import") (part "R0805"))
    )
    (comp (ref "R_OIL")
      (value "52R")
      (footprint "eagle-import:0805")
      (libsource (lib "eagle-import") (part "R0805"))
    )
    (comp (ref "R_OIL_OV")
      (value "1k")
      (footprint "eagle-import:0805")
      (libsource (lib "eagle-import") (part "R0805"))
    )
    (comp (ref "R_OIL_OV1")
      (value "1k")
      (footprint "eagle-import:0805")
      (libsource (lib "eagle-import") (part "R0805"))
    )
    (comp (ref "R_OIL_UP")
      (value "220R")
      (footprint "eagle-import:0805")
      (libsource (lib "eagle-import") (part "R0805"))
    )
    (comp (ref "R_REED")
      (value "7k")
      (footprint "eagle-import:0805")
      (libsource (lib "eagle-import") (part "R0805"))
    )
    (comp (ref "R_REED_DOWN")
      (value "5k (12V Honda Signal) / 100nF (Reed)")
      (footprint "eagle-import:0805")
      (libsource (lib "eagle-import") (part "R0805"))
    )
    (comp (ref "R_REED_UP")
      (value "n.b.(Honda Signal) / 5k (Reed)")
      (footprint "eagle-import:0805")
      (libsource (lib "eagle-import") (part "R0805"))
    )
    (comp (ref "R_RES_UP")
      (value "10k")
      (footprint "eagle-import:0805")
      (libsource (lib "eagle-import") (part "R0805"))
    )
    (comp (ref "R_R_LED_0")
      (value "52R")
      (footprint "eagle-import:0805")
      (libsource (lib "eagle-import") (part "R0805"))
    )
    (comp (ref "R_R_LED_1")
      (value "92R")
      (footprint "eagle-import:0805")
      (libsource (lib "eagle-import") (part "R0805"))
    )
    (comp (ref "R_R_LED_2")
      (value "92R")
      (footprint "eagle-import:0805")
      (libsource (lib "eagle-import") (part "R0805"))
    )
    (comp (ref "R_R_LED_3")
      (value "92R")
      (footprint "eagle-import:0805")
      (libsource (lib "eagle-import") (part "R0805"))
    )
    (comp (ref "R_R_LED_4")
      (value "92R")
      (footprint "eagle-import:0805")
      (libsource (lib "eagle-import") (part "R0805"))
    )
    (comp (ref "R_R_LED_5")
      (value "92R")
      (footprint "eagle-import:0805")
      (libsource (lib "eagle-import") (part "R0805"))
    )
    (comp (ref "R_R_LED_6")
      (value "92R")
      (footprint "eagle-import:0805")
      (libsource (lib "eagle-import") (part "R0805"))
    )
    (comp (ref "R_R_LED_7")
      (value "92R")
      (footprint "eagle-import:0805")
      (libsource (lib "eagle-import") (part "R0805"))
    )
    (comp (ref "R_R_LED_8")
      (value "92R")
      (footprint "eagle-import:0805")
      (libsource (lib "eagle-import") (part "R0805"))
    )
    (comp (ref "R_R_LED_9")
      (value "92R")
      (footprint "eagle-import:0805")
      (libsource (lib "eagle-import") (part "R0805"))
    )
    (comp (ref "R_R_LED_10")
      (value "92R")
      (footprint "eagle-import:0805")
      (libsource (lib "eagle-import") (part "R0805"))
    )
    (comp (ref "R_R_LED_11")
      (value "92R")
      (footprint "eagle-import:0805")
      (libsource (lib "eagle-import") (part "R0805"))
    )
    (comp (ref "R_R_LED_12")
      (value "220R")
      (footprint "eagle-import:0805")
      (libsource (lib "eagle-import") (part "R0805"))
    )
    (comp (ref "R_SCL_UP")
      (value "1k")
      (footprint "eagle-import:0805")
      (libsource (lib "eagle-import") (part "R0805"))
    )
    (comp (ref "R_SDA_UP")
      (value "1k")
      (footprint "eagle-import:0805")
      (libsource (lib "eagle-import") (part "R0805"))
    )
    (comp (ref "R_SD_PWR_UP")
      (value "10k")
      (footprint "eagle-import:0805")
      (libsource (lib "eagle-import") (part "R0805"))
    )
    (comp (ref "R_TEMP_OS")
      (value "10K")
      (footprint "eagle-import:0805")
      (libsource (lib "eagle-import") (part "R0805"))
    )
    (comp (ref "R_TX_DOWN")
      (value "2k7")
      (footprint "eagle-import:0805")
      (libsource (lib "eagle-import") (part "R0805"))
    )
    (comp (ref "R_TX_UP")
      (value "1k2")
      (footprint "eagle-import:0805")
      (libsource (lib "eagle-import") (part "R0805"))
    )
    (comp (ref "R_V_HIGH")
      (value "2k2")
      (footprint "eagle-import:0805")
      (libsource (lib "eagle-import") (part "R0805"))
    )
    (comp (ref "R_V_LOW")
      (value "1k")
      (footprint "eagle-import:0805")
      (libsource (lib "eagle-import") (part "R0805"))
    )
    (comp (ref "R_WATER_UP")
      (value "390R")
      (footprint "eagle-import:0805")
      (libsource (lib "eagle-import") (part "R0805"))
    )
    (comp (ref "S1")
      (value "SW-TASTERECO-DIAGONAL")
      (footprint "eagle-import:SW-ECO")
      (libsource (lib "eagle-import") (part "SW-TASTERECO-DIAGONAL"))
    )
    (comp (ref "SPEEDOSTECKER")
      (value "SPEEDOSTECKER")
      (footprint "eagle-import:SPEEDOSTECKER")
      (libsource (lib "eagle-import") (part "SPEEDOSTECKER"))
    )
    (comp (ref "ST2")
      (value "SD_MICRO")
      (footprint "eagle-import:SD_MICRO")
      (libsource (lib "eagle-import") (part "SD_MICRO"))
    )
    (comp (ref "STEPPER")
      (value "STEPPER")
      (footprint "eagle-import:STEPPER")
      (libsource (lib "eagle-import") (part "STEPPER"))
    )
    (comp (ref "T1")
      (value "Mouser: 771-2N7002BK215 , N-Channel, 60V 350mA, SOT-23, 0,052€")
      (footprint "eagle-import:SOT23")
      (libsource (lib "eagle-import") (part "2N7002"))
    )
    (comp (ref "T2")
      (value "Mouser: 771-2N7002BK215 , N-Channel, 60V 350mA, SOT-23, 0,052€")
      (footprint "eagle-import:SOT23")
      (libsource (lib "eagle-import") (part "2N7002"))
    )
    (comp (ref "T3")
      (value "Mouser: 771-2N7002BK215 , N-Channel, 60V 350mA, SOT-23, 0,052€")
      (footprint "eagle-import:SOT23")
      (libsource (lib "eagle-import") (part "2N7002"))
    )
    (comp (ref "T5")
      (value "Mouser: 771-2N7002BK215 , N-Channel, 60V 350mA, SOT-23, 0,052€")
      (footprint "eagle-import:SOT-23")
      (libsource (lib "eagle-import") (part "T-P-FETBSS139"))
    )
    (comp (ref "T6")
      (value "Mouser: 771-2N7002BK215 , N-Channel, 60V 350mA, SOT-23, 0,052€")
      (footprint "eagle-import:SOT23")
      (libsource (lib "eagle-import") (part "2N7002"))
    )
    (comp (ref "T7")
      (value "Mouser: 771-2N7002BK215 , N-Channel, 60V 350mA, SOT-23, 0,052€")
      (footprint "eagle-import:SOT23")
      (libsource (lib "eagle-import") (part "2N7002"))
    )
    (comp (ref "T8")
      (value "Mouser: 771-2N7002BK215 , N-Channel, 60V 350mA, SOT-23, 0,052€")
      (footprint "eagle-import:SOT23")
      (libsource (lib "eagle-import") (part "2N7002"))
    )
    (comp (ref "T9")
      (value "Mouser: 771-2N7002BK215 , N-Channel, 60V 350mA, SOT-23, 0,052€")
      (footprint "eagle-import:SOT23")
      (libsource (lib "eagle-import") (part "2N7002"))
    )
    (comp (ref "T10")
      (value "Mouser: 771-2N7002BK215 , N-Channel, 60V 350mA, SOT-23, 0,052€")
      (footprint "eagle-import:SOT23")
      (libsource (lib "eagle-import") (part "2N7002"))
    )
    (comp (ref "T11")
      (value "Mouser: 771-2N7002BK215 , N-Channel, 60V 350mA, SOT-23, 0,052€")
      (footprint "eagle-import:SOT23")
      (libsource (lib "eagle-import") (part "2N7002"))
    )
    (comp (ref "T12")
      (value "Mouser: 771-2N7002BK215 , N-Channel, 60V 350mA, SOT-23, 0,052€")
      (footprint "eagle-import:SOT23")
      (libsource (lib "eagle-import") (part "2N7002"))
    )
    (comp (ref "T13")
      (value "Mouser: 771-2N7002BK215 , N-Channel, 60V 350mA, SOT-23, 0,052€")
      (footprint "eagle-import:SOT23")
      (libsource (lib "eagle-import") (part "2N7002"))
    )
    (comp (ref "TEMP_SENS")
      (value "SE95D")
      (footprint "eagle-import:SOIC8")
      (libsource (lib "eagle-import") (part "SE95D"))
    )
    (comp (ref "TX")
      (value "PINHD-1X2")
      (footprint "eagle-import:1X02")
      (libsource (lib "eagle-import") (part "PINHD-1X2"))
    )
    (comp (ref "TX1")
      (value "PINHD-1X2")
      (footprint "eagle-import:1X02")
      (libsource (lib "eagle-import") (part "PINHD-1X2"))
    )
    (comp (ref "TX2")
      (value "PINHD-1X3")
      (footprint "eagle-import:1X03")
      (libsource (lib "eagle-import") (part "PINHD-1X3"))
    )
    (comp (ref "T_P_BRIDGE")
      (value "PMV160UP215")
      (footprint "eagle-import:SOT23")
      (libsource (lib "eagle-import") (part "PMV160UP215"))
    )
    (comp (ref "T_P_BRIDGE1")
      (value "PMV160UP215")
      (footprint "eagle-import:SOT23")
      (libsource (lib "eagle-import") (part "PMV160UP215"))
    )
    (comp (ref "U$1")
      (value "ATMEGA328P-AU")
      (footprint "eagle-import:TQFP8")
      (libsource (lib "eagle-import") (part "ATMEGA328P-AU"))
    )
    (comp (ref "U$3")
      (value "CLM4B-BKW-CTBVA363")
      (footprint "eagle-import:PLCC-4")
      (libsource (lib "eagle-import") (part "CLM4B-BKW-CTBVA363"))
    )
    (comp (ref "U$11")
      (value "CLM4B-RKW-CWAXBAA3")
      (footprint "eagle-import:PLCC-4")
      (libsource (lib "eagle-import") (part "CLM4B-RKW-CWAXBAA3"))
    )
    (comp (ref "U$14")
      (value "74LVC_LVCH245A")
      (footprint "eagle-import:TSSOP20")
      (libsource (lib "eagle-import") (part "74LVC_LVCH245A"))
    )
    (comp (ref "U$19")
      (value "MCP23017")
      (footprint "eagle-import:SOIC28")
      (libsource (lib "eagle-import") (part "MCP23017"))
    )
    (comp (ref "U$22")
      (value "CLM4B-RKW-CWAXBAA3")
      (footprint "eagle-import:PLCC-4")
      (libsource (lib "eagle-import") (part "CLM4B-RKW-CWAXBAA3"))
    )
  )
  (nets
    (net (code "1") (name "+3V3_EXT") (class "Default")
      (node (ref "3.3V_SUPPLY") (pin "OUT") (pinfunction "OUT_OUT") (pintype "bidirectional"))
      (node (ref "BLUETOOTH") (pin "P$17") (pinfunction "P$17_VCC_P$17") (pintype "power_in"))
      (node (ref "BLUETOOTH") (pin "P$2") (pinfunction "P$2_PVCC_P$2") (pintype "power_in"))
      (node (ref "C10") (pin "2") (pinfunction "2_2") (pintype "passive"))
      (node (ref "C12") (pin "2") (pinfunction "2_2") (pintype "passive"))
      (node (ref "C13") (pin "2") (pinfunction "2_2") (pintype "passive"))
      (node (ref "C36") (pin "2") (pinfunction "2_2") (pintype "passive"))
      (node (ref "C4") (pin "2") (pinfunction "2_2") (pintype "passive"))
      (node (ref "GPS") (pin "EN") (pinfunction "EN_EN") (pintype "bidirectional"))
      (node (ref "GPS") (pin "VCC") (pinfunction "VCC_VCC") (pintype "bidirectional"))
      (node (ref "GPS_C1") (pin "2") (pinfunction "2_2") (pintype "passive"))
      (node (ref "GPS_C5") (pin "2") (pinfunction "2_2") (pintype "passive"))
      (node (ref "NHD_2.7") (pin "VDD0") (pinfunction "VDD_VDD0") (pintype "power_in"))
      (node (ref "PWR") (pin "1") (pinfunction "1_1") (pintype "passive"))
      (node (ref "R_SD_PWR_UP") (pin "1") (pinfunction "1_1") (pintype "passive"))
      (node (ref "T5") (pin "2") (pinfunction "S_2") (pintype "bidirectional"))
      (node (ref "T_P_BRIDGE1") (pin "2") (pinfunction "S_2") (pintype "passive"))
      (node (ref "U$14") (pin "1") (pinfunction "DIR_1") (pintype "bidirectional"))
      (node (ref "U$14") (pin "20") (pinfunction "VCC_20") (pintype "bidirectional"))
    )
    (net (code "2") (name "/+3V3_EXT_S") (class "Default")
      (node (ref "C19") (pin "2") (pinfunction "2_2") (pintype "passive"))
      (node (ref "ST2") (pin "4") (pinfunction "VDD_4") (pintype "bidirectional"))
      (node (ref "T_P_BRIDGE1") (pin "3") (pinfunction "D_3") (pintype "passive"))
    )
    (net (code "3") (name "/12V") (class "Default")
      (node (ref "D_VERPOL") (pin "A") (pinfunction "A_A") (pintype "passive"))
      (node (ref "R_V_HIGH") (pin "1") (pinfunction "1_1") (pintype "passive"))
      (node (ref "SPEEDOSTECKER") (pin "P$15") (pinfunction "IGN_VIN_P$15") (pintype "power_in"))
    )
    (net (code "4") (name "/12V_D_SAFE") (class "Default")
      (node (ref "12V_F1") (pin "P$1") (pinfunction "P$1_P$1") (pintype "bidirectional"))
      (node (ref "D_VERPOL") (pin "K") (pinfunction "K_K") (pintype "passive"))
      (node (ref "D_VERPOL1") (pin "K") (pinfunction "K_K") (pintype "passive"))
    )
    (net (code "5") (name "/A0") (class "Default")
      (node (ref "D3") (pin "3") (pinfunction "C_3") (pintype "passive"))
      (node (ref "IC4") (pin "97") (pinfunction "(ADC0)PF0_97") (pintype "bidirectional"))
      (node (ref "R_OIL_OV1") (pin "2") (pinfunction "2_2") (pintype "passive"))
    )
    (net (code "6") (name "/A1") (class "Default")
      (node (ref "D20") (pin "3") (pinfunction "C_3") (pintype "passive"))
      (node (ref "IC4") (pin "96") (pinfunction "(ADC1)PF1_96") (pintype "bidirectional"))
      (node (ref "R_OIL_OV") (pin "2") (pinfunction "2_2") (pintype "passive"))
    )
    (net (code "7") (name "/A2") (class "Default")
      (node (ref "D13") (pin "3") (pinfunction "C_3") (pintype "passive"))
      (node (ref "GPS_C3") (pin "2") (pinfunction "2_2") (pintype "passive"))
      (node (ref "GPS_C4") (pin "2") (pinfunction "2_2") (pintype "passive"))
      (node (ref "IC4") (pin "95") (pinfunction "(ADC2)PF2_95") (pintype "bidirectional"))
      (node (ref "R_V_HIGH") (pin "2") (pinfunction "2_2") (pintype "passive"))
      (node (ref "R_V_LOW") (pin "1") (pinfunction "1_1") (pintype "passive"))
      (node (ref "U$1") (pin "2") (pinfunction "(PCINT20/XCK/T0)PD4_2") (pintype "bidirectional"))
    )
    (net (code "8") (name "/A3") (class "Default")
      (node (ref "IC4") (pin "94") (pinfunction "(ADC3)PF3_94") (pintype "bidirectional"))
    )
    (net (code "9") (name "/A4") (class "Default")
      (node (ref "IC4") (pin "93") (pinfunction "(ADC4/TCK)PF4_93") (pintype "bidirectional"))
    )
    (net (code "10") (name "/A5") (class "Default")
      (node (ref "IC4") (pin "92") (pinfunction "(ADC5/TMS)PF5_92") (pintype "bidirectional"))
    )
    (net (code "11") (name "/A6") (class "Default")
      (node (ref "IC4") (pin "91") (pinfunction "(ADC6/TDO)PF6_91") (pintype "bidirectional"))
    )
    (net (code "12") (name "/A7") (class "Default")
      (node (ref "D22") (pin "3") (pinfunction "C_3") (pintype "passive"))
      (node (ref "IC4") (pin "90") (pinfunction "(ADC7/TDI)PF7_90") (pintype "bidirectional"))
      (node (ref "R_E2_0") (pin "2") (pinfunction "2_2") (pintype "passive"))
      (node (ref "R_E2_1") (pin "2") (pinfunction "2_2") (pintype "passive"))
      (node (ref "R_E2_2") (pin "1") (pinfunction "1_1") (pintype "passive"))
    )
    (net (code "13") (name "/A11") (class "Default")
      (node (ref "IC4") (pin "86") (pinfunction "PK3(ADC11/PCINT19)_86") (pintype "bidirectional"))
    )
    (net (code "14") (name "/A12") (class "Default")
      (node (ref "IC4") (pin "85") (pinfunction "PK4(ADC12/PCINT20)_85") (pintype "bidirectional"))
      (node (ref "TX1") (pin "2") (pinfunction "2_2") (pintype "passive"))
    )
    (net (code "15") (name "/A13") (class "Default")
      (node (ref "IC4") (pin "84") (pinfunction "PK5(ADC13/PCINT21)_84") (pintype "bidirectional"))
      (node (ref "R_BL_L1") (pin "1") (pinfunction "1_1") (pintype "passive"))
      (node (ref "TX1") (pin "1") (pinfunction "1_1") (pintype "passive"))
      (node (ref "TX2") (pin "1") (pinfunction "1_1") (pintype "passive"))
    )
    (net (code "16") (name "/A14") (class "Default")
      (node (ref "IC4") (pin "83") (pinfunction "PK6(ADC14/PCINT22)_83") (pintype "bidirectional"))
    )
    (net (code "17") (name "/A15") (class "Default")
      (node (ref "IC4") (pin "82") (pinfunction "PK7(ADC15/PCINT23)_82") (pintype "bidirectional"))
    )
    (net (code "18") (name "/ANT") (class "Default")
      (node (ref "BLUETOOTH") (pin "P$37") (pinfunction "P$37_RF-IO-ANTENNA_P$37") (pintype "bidirectional"))
    )
    (net (code "19") (name "/ARD_RES_OUT") (class "Default")
      (node (ref "C35") (pin "1") (pinfunction "1_1") (pintype "passive"))
      (node (ref "IC4") (pin "30") (pinfunction "RESET_30") (pintype "input"))
      (node (ref "JP1") (pin "2") (pinfunction "2_2") (pintype "passive"))
      (node (ref "R_RES_UP") (pin "1") (pinfunction "1_1") (pintype "passive"))
      (node (ref "S1") (pin "4") (pinfunction "2_4") (pintype "passive"))
      (node (ref "U$1") (pin "28") (pinfunction "(ADC5/PCINT13/SCL)PC5_28") (pintype "output"))
    )
    (net (code "20") (name "/ARD_RX_5") (class "Default")
      (node (ref "RX_H") (pin "1") (pinfunction "1_1") (pintype "passive"))
      (node (ref "TX") (pin "1") (pinfunction "1_1") (pintype "passive"))
    )
    (net (code "21") (name "/ARD_RX_33") (class "Default")
      (node (ref "BLUETOOTH") (pin "P$26") (pinfunction "P$26UART-RX_P$26") (pintype "input"))
      (node (ref "RX_H") (pin "2") (pinfunction "2_2") (pintype "passive"))
      (node (ref "RX_L") (pin "2") (pinfunction "2_2") (pintype "passive"))
    )
    (net (code "22") (name "/BAT+") (class "Default")
      (node (ref "3.3V_SUPPLY") (pin "IN") (pinfunction "IN_IN") (pintype "bidirectional"))
      (node (ref "5V_SUPPLY") (pin "IN") (pinfunction "IN_IN") (pintype "bidirectional"))
      (node (ref "C11") (pin "1") (pinfunction "1_1") (pintype "passive"))
      (node (ref "CP3") (pin "POS") (pinfunction "PLUS_POS") (pintype "power_in"))
      (node (ref "CP4") (pin "POS") (pinfunction "PLUS_POS") (pintype "power_in"))
      (node (ref "L8") (pin "2") (pinfunction "2_2") (pintype "passive"))
    )
    (net (code "23") (name "/BL_L_IN") (class "Default")
      (node (ref "D2") (pin "3") (pinfunction "C_3") (pintype "passive"))
      (node (ref "IC4") (pin "8") (pinfunction "(T3/INT6)PE6_8") (pintype "bidirectional"))
      (node (ref "R_FLASHL") (pin "2") (pinfunction "2_2") (pintype "passive"))
      (node (ref "R_FLASHL_DOWN") (pin "1") (pinfunction "1_1") (pintype "passive"))
    )
    (net (code "24") (name "/BL_L_IN_H") (class "Default")
      (node (ref "R_FLASHL") (pin "1") (pinfunction "1_1") (pintype "passive"))
      (node (ref "SPEEDOSTECKER") (pin "P$10") (pinfunction "FLASH_L_P$10") (pintype "input"))
    )
    (net (code "25") (name "/BL_R_IN") (class "Default")
      (node (ref "D1") (pin "3") (pinfunction "C_3") (pintype "passive"))
      (node (ref "IC4") (pin "9") (pinfunction "(CLKO/ICP3/INT7)PE7_9") (pintype "bidirectional"))
      (node (ref "R_FLASHR") (pin "2") (pinfunction "2_2") (pintype "passive"))
      (node (ref "R_FLASHR_DOWN") (pin "1") (pinfunction "1_1") (pintype "passive"))
    )
    (net (code "26") (name "/BL_R_IN_H") (class "Default")
      (node (ref "R_FLASHR") (pin "1") (pinfunction "1_1") (pintype "passive"))
      (node (ref "SPEEDOSTECKER") (pin "P$4") (pinfunction "FLASH_R_P$4") (pintype "input"))
    )
    (net (code "27") (name "/B_DOWN") (class "Default")
      (node (ref "B_DOWN") (pin "OUT") (pinfunction "OUT_OUT") (pintype "bidirectional"))
      (node (ref "IC4") (pin "68") (pinfunction "PJ5(PCINT14)_68") (pintype "bidirectional"))
    )
    (net (code "28") (name "/B_LEFT") (class "Default")
      (node (ref "B_LEFT") (pin "OUT") (pinfunction "OUT_OUT") (pintype "bidirectional"))
      (node (ref "D12") (pin "3") (pinfunction "C_3") (pintype "passive"))
      (node (ref "D14") (pin "3") (pinfunction "C_3") (pintype "passive"))
    )
    (net (code "29") (name "/B_RIGHT") (class "Default")
      (node (ref "B_RIGHT") (pin "OUT") (pinfunction "OUT_OUT") (pintype "bidirectional"))
      (node (ref "IC4") (pin "69") (pinfunction "PJ6(PCINT15)_69") (pintype "bidirectional"))
    )
    (net (code "30") (name "/B_UP") (class "Default")
      (node (ref "B_UP") (pin "OUT") (pinfunction "OUT_OUT") (pintype "bidirectional"))
      (node (ref "IC4") (pin "66") (pinfunction "PJ3(PCINT12)_66") (pintype "bidirectional"))
    )
    (net (code "31") (name "/CONNECT") (class "Default")
      (node (ref "BLUETOOTH") (pin "P$13") (pinfunction "P$13_PIO(7)_P$13") (pintype "bidirectional"))
      (node (ref "R_CNT") (pin "2") (pinfunction "2_2") (pintype "passive"))
      (node (ref "U$1") (pin "32") (pinfunction "(INT0/PCINT18)PD2_32") (pintype "bidirectional"))
    )
    (net (code "32") (name "/D2") (class "Default")
      (node (ref "IC1") (pin "3") (pinfunction "O_3") (pintype "output"))
      (node (ref "IC4") (pin "6") (pinfunction "(OC3B/INT4)PE4_6") (pintype "bidirectional"))
    )
    (net (code "33") (name "/D3") (class "Default")
      (node (ref "IC1") (pin "11") (pinfunction "O_11") (pintype "output"))
      (node (ref "IC4") (pin "7") (pinfunction "(OC3C/INT5)PE5_7") (pintype "bidirectional"))
    )
    (net (code "34") (name "/D4") (class "Default")
      (node (ref "IC4") (pin "1") (pinfunction "(OC0B)PG5_1") (pintype "bidirectional"))
      (node (ref "R_SD_PWR_UP") (pin "2") (pinfunction "2_2") (pintype "passive"))
      (node (ref "T_P_BRIDGE1") (pin "1") (pinfunction "G_1") (pintype "passive"))
    )
    (net (code "35") (name "/D5") (class "Default")
      (node (ref "IC4") (pin "5") (pinfunction "(OC3A/AIN1)PE3_5") (pintype "bidirectional"))
    )
    (net (code "36") (name "/D6") (class "Default")
      (node (ref "IC4") (pin "15") (pinfunction "PH3(OC4A)_15") (pintype "bidirectional"))
      (node (ref "U$1") (pin "1") (pinfunction "(PCINT19/OC2B/INT1)PD3_1") (pintype "bidirectional"))
    )
    (net (code "37") (name "/D7") (class "Default")
      (node (ref "IC4") (pin "16") (pinfunction "PH4(OC4B)_16") (pintype "bidirectional"))
      (node (ref "R_B_LED_15") (pin "1") (pinfunction "1_1") (pintype "passive"))
      (node (ref "T12") (pin "1") (pinfunction "G_1") (pintype "passive"))
      (node (ref "T3") (pin "1") (pinfunction "G_1") (pintype "passive"))
    )
    (net (code "38") (name "/D8") (class "Default")
      (node (ref "IC4") (pin "17") (pinfunction "PH5(OC4C)_17") (pintype "bidirectional"))
      (node (ref "R_B_LED_14") (pin "1") (pinfunction "1_1") (pintype "passive"))
      (node (ref "T2") (pin "1") (pinfunction "G_1") (pintype "passive"))
    )
    (net (code "39") (name "/D9") (class "Default")
      (node (ref "IC4") (pin "18") (pinfunction "PH6(OC2B)_18") (pintype "bidirectional"))
      (node (ref "R_B_LED_13") (pin "1") (pinfunction "1_1") (pintype "passive"))
      (node (ref "T1") (pin "1") (pinfunction "G_1") (pintype "passive"))
    )
    (net (code "40") (name "/D10") (class "Default")
      (node (ref "IC4") (pin "23") (pinfunction "(OC2A/PCINT4)PB4_23") (pintype "bidirectional"))
    )
    (net (code "41") (name "/D11") (class "Default")
      (node (ref "IC4") (pin "24") (pinfunction "(OC1A/PCINT5)PB5_24") (pintype "bidirectional"))
    )
    (net (code "42") (name "/D12") (class "Default")
      (node (ref "D7") (pin "1") (pinfunction "A_1") (pintype "passive"))
      (node (ref "IC4") (pin "25") (pinfunction "(OC1B/PCINT6)PB6_25") (pintype "bidirectional"))
    )
    (net (code "43") (name "/D13") (class "Default")
      (node (ref "IC4") (pin "26") (pinfunction "(OC0A/OC1C/PCINT7)PB7_26") (pintype "bidirectional"))
      (node (ref "R_B_LED_12") (pin "1") (pinfunction "1_1") (pintype "passive"))
      (node (ref "T11") (pin "1") (pinfunction "G_1") (pintype "passive"))
    )
    (net (code "44") (name "/D22") (class "Default")
      (node (ref "IC4") (pin "78") (pinfunction "(AD0)PA0_78") (pintype "bidirectional"))
    )
    (net (code "45") (name "/D23") (class "Default")
      (node (ref "IC4") (pin "77") (pinfunction "(AD1)PA1_77") (pintype "bidirectional"))
    )
    (net (code "46") (name "/D24") (class "Default")
      (node (ref "GPS_D1") (pin "1") (pinfunction "A_1") (pintype "passive"))
      (node (ref "IC4") (pin "76") (pinfunction "(AD2)PA2_76") (pintype "bidirectional"))
    )
    (net (code "47") (name "/D25") (class "Default")
      (node (ref "IC4") (pin "75") (pinfunction "(AD3)PA3_75") (pintype "bidirectional"))
    )
    (net (code "48") (name "/D26") (class "Default")
      (node (ref "IC4") (pin "74") (pinfunction "(AD4)PA4_74") (pintype "bidirectional"))
    )
    (net (code "49") (name "/D27") (class "Default")
      (node (ref "IC4") (pin "73") (pinfunction "(AD5)PA5_73") (pintype "bidirectional"))
    )
    (net (code "50") (name "/D28") (class "Default")
      (node (ref "IC4") (pin "72") (pinfunction "(AD6)PA6_72") (pintype "bidirectional"))
    )
    (net (code "51") (name "/D29") (class "Default")
      (node (ref "IC4") (pin "71") (pinfunction "(AD7)PA7_71") (pintype "bidirectional"))
    )
    (net (code "52") (name "/D30") (class "Default")
      (node (ref "IC4") (pin "60") (pinfunction "(A15)PC7_60") (pintype "bidirectional"))
      (node (ref "NHD_2.7") (pin "DC") (pinfunction "DC_DC") (pintype "bidirectional"))
    )
    (net (code "53") (name "/D31") (class "Default")
      (node (ref "IC4") (pin "59") (pinfunction "(A14)PC6_59") (pintype "bidirectional"))
    )
    (net (code "54") (name "/D32") (class "Default")
      (node (ref "IC4") (pin "58") (pinfunction "(A13)PC5_58") (pintype "bidirectional"))
      (node (ref "NHD_2.7") (pin "RES") (pinfunction "RES_RES") (pintype "bidirectional"))
    )
    (net (code "55") (name "/D33") (class "Default")
      (node (ref "IC4") (pin "57") (pinfunction "(A12)PC4_57") (pintype "bidirectional"))
    )
    (net (code "56") (name "/D34") (class "Default")
      (node (ref "IC4") (pin "56") (pinfunction "(A11)PC3_56") (pintype "bidirectional"))
      (node (ref "NHD_2.7") (pin "CS") (pinfunction "CS_CS") (pintype "bidirectional"))
    )
    (net (code "57") (name "/D36") (class "Default")
      (node (ref "IC4") (pin "54") (pinfunction "(A9)PC1_54") (pintype "bidirectional"))
      (node (ref "NHD_2.7") (pin "SDIN") (pinfunction "SDA_SDIN") (pintype "bidirectional"))
    )
    (net (code "58") (name "/D38") (class "Default")
      (node (ref "IC4") (pin "50") (pinfunction "(T0)PD7_50") (pintype "bidirectional"))
    )
    (net (code "59") (name "/D39") (class "Default")
      (node (ref "IC4") (pin "70") (pinfunction "(ALE)PG2_70") (pintype "bidirectional"))
    )
    (net (code "60") (name "/D42") (class "Default")
      (node (ref "IC4") (pin "42") (pinfunction "PL7_42") (pintype "bidirectional"))
    )
    (net (code "61") (name "/D43") (class "Default")
      (node (ref "IC4") (pin "41") (pinfunction "PL6_41") (pintype "bidirectional"))
    )
    (net (code "62") (name "/D44") (class "Default")
      (node (ref "IC4") (pin "40") (pinfunction "PL5(OC5C)_40") (pintype "bidirectional"))
    )
    (net (code "63") (name "/D45") (class "Default")
      (node (ref "IC4") (pin "39") (pinfunction "PL4(OC5B)_39") (pintype "bidirectional"))
    )
    (net (code "64") (name "/D46") (class "Default")
      (node (ref "IC4") (pin "38") (pinfunction "PL3(OC5A)_38") (pintype "bidirectional"))
    )
    (net (code "65") (name "/D47") (class "Default")
      (node (ref "IC4") (pin "37") (pinfunction "PL2(T5)_37") (pintype "bidirectional"))
      (node (ref "R_E1_2") (pin "2") (pinfunction "2_2") (pintype "passive"))
      (node (ref "R_E1_4") (pin "2") (pinfunction "2_2") (pintype "passive"))
    )
    (net (code "66") (name "/D48") (class "Default")
      (node (ref "D_P_MCCOI") (pin "3") (pinfunction "C_3") (pintype "passive"))
      (node (ref "IC4") (pin "36") (pinfunction "PL1(ICP5)_36") (pintype "bidirectional"))
      (node (ref "R_HB4") (pin "2") (pinfunction "2_2") (pintype "passive"))
    )
    (net (code "67") (name "/D50") (class "Default")
      (node (ref "IC4") (pin "22") (pinfunction "(MISO/PCINT3)PB3_22") (pintype "bidirectional"))
      (node (ref "JP1") (pin "6") (pinfunction "6_6") (pintype "passive"))
      (node (ref "ST2") (pin "7") (pinfunction "DAT0_7") (pintype "bidirectional"))
    )
    (net (code "68") (name "/D51") (class "Default")
      (node (ref "IC4") (pin "21") (pinfunction "(MOSI/PCINT2)PB2_21") (pintype "bidirectional"))
      (node (ref "JP1") (pin "3") (pinfunction "3_3") (pintype "passive"))
      (node (ref "U$14") (pin "7") (pinfunction "A5_7") (pintype "bidirectional"))
    )
    (net (code "69") (name "/D52") (class "Default")
      (node (ref "IC4") (pin "20") (pinfunction "(SCK/PCINT1)PB1_20") (pintype "bidirectional"))
      (node (ref "JP1") (pin "4") (pinfunction "4_4") (pintype "passive"))
      (node (ref "U$14") (pin "8") (pinfunction "A6_8") (pintype "bidirectional"))
    )
    (net (code "70") (name "/D53") (class "Default")
      (node (ref "IC4") (pin "19") (pinfunction "(SS/PCINT0)PB0_19") (pintype "bidirectional"))
      (node (ref "U$14") (pin "9") (pinfunction "A7_9") (pintype "bidirectional"))
    )
    (net (code "71") (name "/DISP_SCL") (class "Default")
      (node (ref "IC4") (pin "55") (pinfunction "(A10)PC2_55") (pintype "bidirectional"))
      (node (ref "NHD_2.7") (pin "SCLK") (pinfunction "SCL_SCLK") (pintype "bidirectional"))
    )
    (net (code "72") (name "/DZ") (class "Default")
      (node (ref "C8") (pin "1") (pinfunction "1_1") (pintype "passive"))
      (node (ref "D6") (pin "3") (pinfunction "C_3") (pintype "passive"))
      (node (ref "IC1") (pin "2") (pinfunction "I1_2") (pintype "input"))
      (node (ref "R_DZ") (pin "2") (pinfunction "2_2") (pintype "passive"))
      (node (ref "R_DZ_DOWN") (pin "1") (pinfunction "1_1") (pintype "passive"))
    )
    (net (code "73") (name "/DZ_IN") (class "Default")
      (node (ref "R_DZ") (pin "1") (pinfunction "1_1") (pintype "passive"))
      (node (ref "SPEEDOSTECKER") (pin "P$6") (pinfunction "DZ_P$6") (pintype "input"))
    )
    (net (code "74") (name "/HB_IN") (class "Default")
      (node (ref "D8") (pin "3") (pinfunction "C_3") (pintype "passive"))
      (node (ref "IC4") (pin "87") (pinfunction "PK2(ADC10/PCINT18)_87") (pintype "bidirectional"))
      (node (ref "R_HB") (pin "2") (pinfunction "2_2") (pintype "passive"))
      (node (ref "R_HB_DOWN") (pin "1") (pinfunction "1_1") (pintype "passive"))
    )
    (net (code "75") (name "/HB_IN_H") (class "Default")
      (node (ref "R_HB") (pin "1") (pinfunction "1_1") (pintype "passive"))
      (node (ref "SPEEDOSTECKER") (pin "P$1") (pinfunction "HIGH_BEAM_P$1") (pintype "input"))
    )
    (net (code "76") (name "/KUPPLUNG_IN") (class "Default")
      (node (ref "D7") (pin "3") (pinfunction "C_3") (pintype "passive"))
      (node (ref "SPEEDOSTECKER") (pin "P$8") (pinfunction "KUPPLUNG_IN_P$8") (pintype "input"))
    )
    (net (code "77") (name "/M1") (class "Default")
      (node (ref "STEPPER") (pin "1+") (pinfunction "1+_1+") (pintype "bidirectional"))
      (node (ref "U$1") (pin "23") (pinfunction "(ADC0/PCINT8)PC0_23") (pintype "output"))
    )
    (net (code "78") (name "/M2") (class "Default")
      (node (ref "STEPPER") (pin "1-") (pinfunction "1-_1-") (pintype "bidirectional"))
      (node (ref "U$1") (pin "24") (pinfunction "(ADC1/PCINT9)PC1_24") (pintype "output"))
    )
    (net (code "79") (name "/M3") (class "Default")
      (node (ref "STEPPER") (pin "2+") (pinfunction "2+_2+") (pintype "bidirectional"))
      (node (ref "U$1") (pin "25") (pinfunction "(ADC2/PCINT10)PC2_25") (pintype "output"))
    )
    (net (code "80") (name "/M4") (class "Default")
      (node (ref "STEPPER") (pin "2-") (pinfunction "2-_2-") (pintype "bidirectional"))
      (node (ref "U$1") (pin "26") (pinfunction "(ADC3/PCINT11)PC3_26") (pintype "output"))
    )
    (net (code "81") (name "/MISO_AT8") (class "Default")
      (node (ref "JP2") (pin "6") (pinfunction "6_6") (pintype "passive"))
      (node (ref "U$1") (pin "16") (pinfunction "(PCINT4/MISO)PB4_16") (pintype "bidirectional"))
    )
    (net (code "82") (name "/MOSI_AT8") (class "Default")
      (node (ref "JP2") (pin "3") (pinfunction "3_3") (pintype "passive"))
      (node (ref "U$1") (pin "15") (pinfunction "(PCINT3/OC2A/MOSI)PB3_15") (pintype "bidirectional"))
    )
    (net (code "83") (name "/N$44") (class "Default")
      (node (ref "IC4") (pin "53") (pinfunction "(A8)PC0_53") (pintype "bidirectional"))
    )
    (net (code "84") (name "/N$48") (class "Default")
      (node (ref "IC4") (pin "52") (pinfunction "(RD)PG1_52") (pintype "bidirectional"))
    )
    (net (code "85") (name "/N$70") (class "Default")
      (node (ref "R_HB1") (pin "1") (pinfunction "1_1") (pintype "passive"))
      (node (ref "SPEEDOSTECKER") (pin "P$3") (pinfunction "OIL_PRESSURE_P$3") (pintype "input"))
    )
    (net (code "86") (name "/N$110") (class "Default")
      (node (ref "R_HB5") (pin "1") (pinfunction "1_1") (pintype "passive"))
      (node (ref "SPEEDOSTECKER") (pin "P$5") (pinfunction "NEUTRAL_GEAR_P$5") (pintype "input"))
    )
    (net (code "87") (name "/NG_IN") (class "Default")
      (node (ref "D10") (pin "3") (pinfunction "C_3") (pintype "passive"))
      (node (ref "IC4") (pin "88") (pinfunction "PK1(ADC9/PCINT17)_88") (pintype "bidirectional"))
      (node (ref "R_HB5") (pin "2") (pinfunction "2_2") (pintype "passive"))
    )
    (net (code "88") (name "/OIL_PR_IN") (class "Default")
      (node (ref "D21") (pin "3") (pinfunction "C_3") (pintype "passive"))
      (node (ref "IC4") (pin "89") (pinfunction "PK0(ADC8/PCINT16)_89") (pintype "bidirectional"))
      (node (ref "R_HB1") (pin "2") (pinfunction "2_2") (pintype "passive"))
    )
    (net (code "89") (name "/PE_A3") (class "Default")
      (node (ref "R_B_LED_17") (pin "2") (pinfunction "2_2") (pintype "passive"))
      (node (ref "T9") (pin "1") (pinfunction "G_1") (pintype "passive"))
      (node (ref "U$19") (pin "24") (pinfunction "A3_24") (pintype "bidirectional"))
    )
    (net (code "90") (name "/PE_A4") (class "Default")
      (node (ref "R_B_LED_19") (pin "2") (pinfunction "2_2") (pintype "passive"))
      (node (ref "T7") (pin "1") (pinfunction "G_1") (pintype "passive"))
      (node (ref "U$19") (pin "25") (pinfunction "A4_25") (pintype "bidirectional"))
    )
    (net (code "91") (name "/PE_A5") (class "Default")
      (node (ref "R_B_LED_20") (pin "2") (pinfunction "2_2") (pintype "passive"))
      (node (ref "T6") (pin "1") (pinfunction "G_1") (pintype "passive"))
      (node (ref "U$19") (pin "26") (pinfunction "A5_26") (pintype "bidirectional"))
    )
    (net (code "92") (name "/PE_A6") (class "Default")
      (node (ref "R_B_LED_16") (pin "2") (pinfunction "2_2") (pintype "passive"))
      (node (ref "T10") (pin "1") (pinfunction "G_1") (pintype "passive"))
      (node (ref "U$19") (pin "27") (pinfunction "A6_27") (pintype "bidirectional"))
    )
    (net (code "93") (name "/PE_A7") (class "Default")
      (node (ref "R_B_LED_18") (pin "2") (pinfunction "2_2") (pintype "passive"))
      (node (ref "T8") (pin "1") (pinfunction "G_1") (pintype "passive"))
      (node (ref "U$19") (pin "28") (pinfunction "A7_28") (pintype "bidirectional"))
    )
    (net (code "94") (name "/REED_IN") (class "Default")
      (node (ref "R_REED") (pin "1") (pinfunction "1_1") (pintype "passive"))
      (node (ref "SPEEDOSTECKER") (pin "P$9") (pinfunction "REED_P$9") (pintype "input"))
    )
    (net (code "95") (name "/RESETAVR_AT8") (class "Default")
      (node (ref "C9") (pin "1") (pinfunction "1_1") (pintype "passive"))
      (node (ref "IC4") (pin "47") (pinfunction "(ICP1)PD4_47") (pintype "bidirectional"))
      (node (ref "JP2") (pin "2") (pinfunction "2_2") (pintype "passive"))
      (node (ref "R_L3") (pin "2") (pinfunction "2_2") (pintype "passive"))
      (node (ref "U$1") (pin "29") (pinfunction "(~{RESET}/PCINT14)PC6_29") (pintype "output"))
    )
    (net (code "96") (name "/RX0") (class "Default")
      (node (ref "IC4") (pin "2") (pinfunction "(RXD0/PCIN8)PE0_2") (pintype "bidirectional"))
      (node (ref "RX") (pin "1") (pinfunction "1_1") (pintype "passive"))
    )
    (net (code "97") (name "/RX1") (class "Default")
      (node (ref "GPS") (pin "TXD") (pinfunction "TXD_NMEA_OUT_TXD") (pintype "bidirectional"))
      (node (ref "IC4") (pin "45") (pinfunction "(RXD1/INT2)PD2_45") (pintype "bidirectional"))
    )
    (net (code "98") (name "/RX3") (class "Default")
      (node (ref "IC4") (pin "63") (pinfunction "PJ0(RXD3/PCINT9)_63") (pintype "bidirectional"))
      (node (ref "U$1") (pin "31") (pinfunction "(TXD/PCINT17)PD1_31") (pintype "bidirectional"))
    )
    (net (code "99") (name "/SCK_AT8") (class "Default")
      (node (ref "JP2") (pin "4") (pinfunction "4_4") (pintype "passive"))
      (node (ref "U$1") (pin "17") (pinfunction "(PCINT5/SCK)PB5_17") (pintype "bidirectional"))
    )
    (net (code "100") (name "/SCL") (class "Default")
      (node (ref "IC4") (pin "43") (pinfunction "(SCL/INT0)PD0_43") (pintype "bidirectional"))
      (node (ref "R_SCL_UP") (pin "2") (pinfunction "2_2") (pintype "passive"))
      (node (ref "TEMP_SENS") (pin "2") (pinfunction "SCL_2") (pintype "bidirectional"))
      (node (ref "TX2") (pin "3") (pinfunction "3_3") (pintype "passive"))
      (node (ref "U$19") (pin "12") (pinfunction "SCL_12") (pintype "bidirectional"))
    )
    (net (code "101") (name "/SDA") (class "Default")
      (node (ref "IC4") (pin "44") (pinfunction "(SDA/INT1)PD1_44") (pintype "bidirectional"))
      (node (ref "R_SDA_UP") (pin "2") (pinfunction "2_2") (pintype "passive"))
      (node (ref "TEMP_SENS") (pin "1") (pinfunction "SDA_1") (pintype "bidirectional"))
      (node (ref "TX2") (pin "2") (pinfunction "2_2") (pintype "passive"))
      (node (ref "U$19") (pin "13") (pinfunction "SDA_13") (pintype "bidirectional"))
    )
    (net (code "102") (name "/SD_CD") (class "Default")
      (node (ref "ST2") (pin "2") (pinfunction "DAT3/CD_2") (pintype "bidirectional"))
      (node (ref "U$14") (pin "11") (pinfunction "B7_11") (pintype "bidirectional"))
    )
    (net (code "103") (name "/SD_CLK") (class "Default")
      (node (ref "ST2") (pin "5") (pinfunction "CLK_5") (pintype "bidirectional"))
      (node (ref "U$14") (pin "12") (pinfunction "B6_12") (pintype "bidirectional"))
    )
    (net (code "104") (name "/SD_DATA_IN") (class "Default")
      (node (ref "ST2") (pin "3") (pinfunction "CMD_3") (pintype "bidirectional"))
      (node (ref "U$14") (pin "13") (pinfunction "B5_13") (pintype "bidirectional"))
    )
    (net (code "105") (name "/SELF_PWR_UP") (class "Default")
      (node (ref "IC4") (pin "35") (pinfunction "PL0(ICP4)_35") (pintype "bidirectional"))
      (node (ref "R_DEAKT_DAUER_P1") (pin "1") (pinfunction "1_1") (pintype "passive"))
      (node (ref "T13") (pin "1") (pinfunction "G_1") (pintype "passive"))
    )
    (net (code "106") (name "/TX") (class "Default")
      (node (ref "BLUETOOTH") (pin "P$27") (pinfunction "P$27_UART-TX_P$27") (pintype "output"))
      (node (ref "RX") (pin "2") (pinfunction "2_2") (pintype "passive"))
    )
    (net (code "107") (name "/TX0") (class "Default")
      (node (ref "IC4") (pin "3") (pinfunction "(TXD0)PE1_3") (pintype "bidirectional"))
      (node (ref "TX") (pin "2") (pinfunction "2_2") (pintype "passive"))
    )
    (net (code "108") (name "/TX1") (class "Default")
      (node (ref "IC4") (pin "46") (pinfunction "(TXD1/INT3)PD3_46") (pintype "bidirectional"))
      (node (ref "R_TX_UP") (pin "2") (pinfunction "2_2") (pintype "passive"))
    )
    (net (code "109") (name "/TX1_3.3") (class "Default")
      (node (ref "GPS") (pin "RXD") (pinfunction "RXD_RXD") (pintype "bidirectional"))
      (node (ref "R_TX_DOWN") (pin "1") (pinfunction "1_1") (pintype "passive"))
      (node (ref "R_TX_UP") (pin "1") (pinfunction "1_1") (pintype "passive"))
    )
    (net (code "110") (name "/TX3") (class "Default")
      (node (ref "IC4") (pin "64") (pinfunction "PJ1(TXD3/PCINT10)_64") (pintype "bidirectional"))
      (node (ref "U$1") (pin "30") (pinfunction "(RXD/PCINT16)PD0_30") (pintype "bidirectional"))
    )
    (net (code "111") (name "/V_AT8_BUFFERED") (class "Default")
      (node (ref "AT8_REF") (pin "1") (pinfunction "1_1") (pintype "passive"))
      (node (ref "C2") (pin "2") (pinfunction "2_2") (pintype "passive"))
      (node (ref "C3") (pin "2") (pinfunction "2_2") (pintype "passive"))
      (node (ref "C_EMERGENCY") (pin "PLUS") (pinfunction "PLUS_PLUS") (pintype "power_in"))
      (node (ref "D9") (pin "C") (pinfunction "C_C") (pintype "passive"))
      (node (ref "JP2") (pin "5") (pinfunction "5_5") (pintype "passive"))
      (node (ref "U$1") (pin "4") (pinfunction "VCC_4") (pintype "power_in"))
      (node (ref "U$1") (pin "6") (pinfunction "VCC_6") (pintype "power_in"))
    )
    (net (code "112") (name "GND") (class "Default")
      (node (ref "3.3V_SUPPLY") (pin "GND") (pinfunction "GND_GND") (pintype "bidirectional"))
      (node (ref "5V_SUPPLY") (pin "GND") (pinfunction "GND_GND") (pintype "bidirectional"))
      (node (ref "BLUETOOTH") (pin "P$1") (pinfunction "P$1_GND_P$1") (pintype "power_in"))
      (node (ref "BLUETOOTH") (pin "P$10") (pinfunction "P$10_GND_P$10") (pintype "power_in"))
      (node (ref "BLUETOOTH") (pin "P$18") (pinfunction "P$18_GND_P$18") (pintype "power_in"))
      (node (ref "BLUETOOTH") (pin "P$19") (pinfunction "P$19_GND_P$19") (pintype "power_in"))
      (node (ref "BLUETOOTH") (pin "P$29") (pinfunction "P$29_GND_P$29") (pintype "power_in"))
      (node (ref "BLUETOOTH") (pin "P$38") (pinfunction "P$38_GND_P$38") (pintype "power_in"))
      (node (ref "BLUETOOTH") (pin "P$AGND") (pinfunction "P$AGND_P$AGND") (pintype "power_in"))
      (node (ref "BLUETOOTH") (pin "P$BGND") (pinfunction "P$BGND_P$BGND") (pintype "power_in"))
      (node (ref "B_DOWN") (pin "IN") (pinfunction "IN_IN") (pintype "bidirectional"))
      (node (ref "B_DOWN") (pin "IN2") (pinfunction "IN_IN2") (pintype "bidirectional"))
      (node (ref "B_LEFT") (pin "IN") (pinfunction "IN_IN") (pintype "bidirectional"))
      (node (ref "B_LEFT") (pin "IN2") (pinfunction "IN_IN2") (pintype "bidirectional"))
      (node (ref "B_RIGHT") (pin "IN") (pinfunction "IN_IN") (pintype "bidirectional"))
      (node (ref "B_RIGHT") (pin "IN2") (pinfunction "IN_IN2") (pintype "bidirectional"))
      (node (ref "B_UP") (pin "IN") (pinfunction "IN_IN") (pintype "bidirectional"))
      (node (ref "B_UP") (pin "IN2") (pinfunction "IN_IN2") (pintype "bidirectional"))
      (node (ref "C1") (pin "2") (pinfunction "2_2") (pintype "passive"))
      (node (ref "C10") (pin "1") (pinfunction "1_1") (pintype "passive"))
      (node (ref "C11") (pin "2") (pinfunction "2_2") (pintype "passive"))
      (node (ref "C12") (pin "1") (pinfunction "1_1") (pintype "passive"))
      (node (ref "C13") (pin "1") (pinfunction "1_1") (pintype "passive"))
      (node (ref "C18") (pin "2") (pinfunction "2_2") (pintype "passive"))
      (node (ref "C19") (pin "1") (pinfunction "1_1") (pintype "passive"))
      (node (ref "C2") (pin "1") (pinfunction "1_1") (pintype "passive"))
      (node (ref "C3") (pin "1") (pinfunction "1_1") (pintype "passive"))
      (node (ref "C31") (pin "2") (pinfunction "2_2") (pintype "passive"))
      (node (ref "C32") (pin "2") (pinfunction "2_2") (pintype "passive"))
      (node (ref "C33") (pin "2") (pinfunction "2_2") (pintype "passive"))
      (node (ref "C34") (pin "2") (pinfunction "2_2") (pintype "passive"))
      (node (ref "C35") (pin "2") (pinfunction "2_2") (pintype "passive"))
      (node (ref "C36") (pin "1") (pinfunction "1_1") (pintype "passive"))
      (node (ref "C39") (pin "2") (pinfunction "2_2") (pintype "passive"))
      (node (ref "C4") (pin "1") (pinfunction "1_1") (pintype "passive"))
      (node (ref "C5") (pin "2") (pinfunction "2_2") (pintype "passive"))
      (node (ref "C6") (pin "2") (pinfunction "2_2") (pintype "passive"))
      (node (ref "C7") (pin "2") (pinfunction "2_2") (pintype "passive"))
      (node (ref "C8") (pin "2") (pinfunction "2_2") (pintype "passive"))
      (node (ref "C9") (pin "2") (pinfunction "2_2") (pintype "passive"))
      (node (ref "CP1") (pin "NEG") (pinfunction "GND_NEG") (pintype "power_in"))
      (node (ref "CP2") (pin "NEG") (pinfunction "GND_NEG") (pintype "power_in"))
      (node (ref "CP3") (pin "NEG") (pinfunction "GND_NEG") (pintype "power_in"))
      (node (ref "CP4") (pin "NEG") (pinfunction "GND_NEG") (pintype "power_in"))
      (node (ref "C_EMERGENCY") (pin "MINUS") (pinfunction "GND_MINUS") (pintype "power_in"))
      (node (ref "C_QUA_4") (pin "1") (pinfunction "1_1") (pintype "passive"))
      (node (ref "C_QUA_5") (pin "1") (pinfunction "1_1") (pintype "passive"))
      (node (ref "D1") (pin "1") (pinfunction "A_1") (pintype "passive"))
      (node (ref "D10") (pin "1") (pinfunction "A_1") (pintype "passive"))
      (node (ref "D13") (pin "1") (pinfunction "A_1") (pintype "passive"))
      (node (ref "D18") (pin "1") (pinfunction "A_1") (pintype "passive"))
      (node (ref "D2") (pin "1") (pinfunction "A_1") (pintype "passive"))
      (node (ref "D20") (pin "1") (pinfunction "A_1") (pintype "passive"))
      (node (ref "D21") (pin "1") (pinfunction "A_1") (pintype "passive"))
      (node (ref "D22") (pin "1") (pinfunction "A_1") (pintype "passive"))
      (node (ref "D3") (pin "1") (pinfunction "A_1") (pintype "passive"))
      (node (ref "D4") (pin "2") (pinfunction "K_2") (pintype "passive"))
      (node (ref "D5") (pin "2") (pinfunction "K_2") (pintype "passive"))
      (node (ref "D6") (pin "1") (pinfunction "A_1") (pintype "passive"))
      (node (ref "D8") (pin "1") (pinfunction "A_1") (pintype "passive"))
      (node (ref "D_GPS_FIX") (pin "2") (pinfunction "K_2") (pintype "passive"))
      (node (ref "D_L0") (pin "2") (pinfunction "K_2") (pintype "passive"))
      (node (ref "D_L1") (pin "2") (pinfunction "K_2") (pintype "passive"))
      (node (ref "D_L2") (pin "2") (pinfunction "K_2") (pintype "passive"))
      (node (ref "D_PWR_LED") (pin "2") (pinfunction "K_2") (pintype "passive"))
      (node (ref "D_P_MCCOI") (pin "1") (pinfunction "A_1") (pintype "passive"))
      (node (ref "GPS") (pin "GND") (pinfunction "GND_GND") (pintype "bidirectional"))
      (node (ref "GPS") (pin "GND2") (pinfunction "GND2_GND2") (pintype "bidirectional"))
      (node (ref "GPS") (pin "GND_3") (pinfunction "GND_3_GND_3") (pintype "bidirectional"))
      (node (ref "GPS") (pin "GND_4") (pinfunction "GND_4_GND_4") (pintype "bidirectional"))
      (node (ref "GPS") (pin "GND_5") (pinfunction "GND_5_GND_5") (pintype "bidirectional"))
      (node (ref "GPS_BAT") (pin "GND") (pinfunction "-_GND") (pintype "power_in"))
      (node (ref "GPS_C1") (pin "1") (pinfunction "1_1") (pintype "passive"))
      (node (ref "GPS_C2") (pin "2") (pinfunction "2_2") (pintype "passive"))
      (node (ref "GPS_C3") (pin "1") (pinfunction "1_1") (pintype "passive"))
      (node (ref "GPS_C4") (pin "1") (pinfunction "1_1") (pintype "passive"))
      (node (ref "GPS_C5") (pin "1") (pinfunction "1_1") (pintype "passive"))
      (node (ref "IC1") (pin "7") (pinfunction "VSS_7") (pintype "power_in"))
      (node (ref "IC4") (pin "11") (pinfunction "GND_11") (pintype "power_in"))
      (node (ref "IC4") (pin "32") (pinfunction "GND1_32") (pintype "power_in"))
      (node (ref "IC4") (pin "51") (pinfunction "(WR)PG0_51") (pintype "bidirectional"))
      (node (ref "IC4") (pin "62") (pinfunction "GND2_62") (pintype "power_in"))
      (node (ref "IC4") (pin "81") (pinfunction "GND3_81") (pintype "power_in"))
      (node (ref "IC4") (pin "99") (pinfunction "AGND_99") (pintype "power_in"))
      (node (ref "JP1") (pin "1") (pinfunction "1_1") (pintype "passive"))
      (node (ref "JP2") (pin "1") (pinfunction "1_1") (pintype "passive"))
      (node (ref "NHD_2.7") (pin "GND0") (pinfunction "GND_GND0") (pintype "power_in"))
      (node (ref "NHD_2.7") (pin "GND1") (pinfunction "GND2_GND1") (pintype "power_in"))
      (node (ref "NHD_2.7") (pin "GND2") (pinfunction "GND3_GND2") (pintype "power_in"))
      (node (ref "NHD_2.7") (pin "GND3") (pinfunction "GND4_GND3") (pintype "power_in"))
      (node (ref "NHD_2.7") (pin "GND4") (pinfunction "GND5_GND4") (pintype "power_in"))
      (node (ref "NHD_2.7") (pin "GND5") (pinfunction "GND6_GND5") (pintype "power_in"))
      (node (ref "NHD_2.7") (pin "GND6") (pinfunction "GND7_GND6") (pintype "power_in"))
      (node (ref "NHD_2.7") (pin "GND7") (pinfunction "GND8_GND7") (pintype "power_in"))
      (node (ref "NHD_2.7") (pin "GND8") (pinfunction "GND9_GND8") (pintype "power_in"))
      (node (ref "NHD_2.7") (pin "GND9") (pinfunction "GND10_GND9") (pintype "power_in"))
      (node (ref "PE") (pin "1") (pinfunction "1_1") (pintype "passive"))
      (node (ref "PWR") (pin "3") (pinfunction "3_3") (pintype "passive"))
      (node (ref "PWR1") (pin "1") (pinfunction "1_1") (pintype "passive"))
      (node (ref "RX_L") (pin "1") (pinfunction "1_1") (pintype "passive"))
      (node (ref "R_BL_L1") (pin "2") (pinfunction "2_2") (pintype "passive"))
      (node (ref "R_B_LED_12") (pin "2") (pinfunction "2_2") (pintype "passive"))
      (node (ref "R_B_LED_13") (pin "2") (pinfunction "2_2") (pintype "passive"))
      (node (ref "R_B_LED_14") (pin "2") (pinfunction "2_2") (pintype "passive"))
      (node (ref "R_B_LED_15") (pin "2") (pinfunction "2_2") (pintype "passive"))
      (node (ref "R_B_LED_16") (pin "1") (pinfunction "1_1") (pintype "passive"))
      (node (ref "R_B_LED_17") (pin "1") (pinfunction "1_1") (pintype "passive"))
      (node (ref "R_B_LED_18") (pin "1") (pinfunction "1_1") (pintype "passive"))
      (node (ref "R_B_LED_19") (pin "1") (pinfunction "1_1") (pintype "passive"))
      (node (ref "R_B_LED_20") (pin "1") (pinfunction "1_1") (pintype "passive"))
      (node (ref "R_DEAKT_DAUER_P1") (pin "2") (pinfunction "2_2") (pintype "passive"))
      (node (ref "R_DZ_DOWN") (pin "2") (pinfunction "2_2") (pintype "passive"))
      (node (ref "R_E1_3") (pin "1") (pinfunction "1_1") (pintype "passive"))
      (node (ref "R_E2_2") (pin "2") (pinfunction "2_2") (pintype "passive"))
      (node (ref "R_FLASHL_DOWN") (pin "2") (pinfunction "2_2") (pintype "passive"))
      (node (ref "R_FLASHR_DOWN") (pin "2") (pinfunction "2_2") (pintype "passive"))
      (node (ref "R_HB_DOWN") (pin "2") (pinfunction "2_2") (pintype "passive"))
      (node (ref "R_REED_DOWN") (pin "2") (pinfunction "2_2") (pintype "passive"))
      (node (ref "R_R_LED_12") (pin "1") (pinfunction "1_1") (pintype "passive"))
      (node (ref "R_TX_DOWN") (pin "2") (pinfunction "2_2") (pintype "passive"))
      (node (ref "R_V_LOW") (pin "2") (pinfunction "2_2") (pintype "passive"))
      (node (ref "S1") (pin "1") (pinfunction "1_1") (pintype "passive"))
      (node (ref "SPEEDOSTECKER") (pin "P$11") (pinfunction "GND_P$11") (pintype "power_in"))
      (node (ref "ST2") (pin "6") (pinfunction "GND_6") (pintype "bidirectional"))
      (node (ref "ST2") (pin "GND") (pinfunction "SCHIRM1_GND") (pintype "bidirectional"))
      (node (ref "ST2") (pin "GND2") (pinfunction "SCHIRM2_GND2") (pintype "bidirectional"))
      (node (ref "ST2") (pin "GND3") (pinfunction "SCHIRM3_GND3") (pintype "bidirectional"))
      (node (ref "ST2") (pin "GND4") (pinfunction "SCHIRM_GND4") (pintype "bidirectional"))
      (node (ref "T1") (pin "2") (pinfunction "S_2") (pintype "passive"))
      (node (ref "T10") (pin "2") (pinfunction "S_2") (pintype "passive"))
      (node (ref "T11") (pin "2") (pinfunction "S_2") (pintype "passive"))
      (node (ref "T12") (pin "2") (pinfunction "S_2") (pintype "passive"))
      (node (ref "T13") (pin "2") (pinfunction "S_2") (pintype "passive"))
      (node (ref "T2") (pin "2") (pinfunction "S_2") (pintype "passive"))
      (node (ref "T3") (pin "2") (pinfunction "S_2") (pintype "passive"))
      (node (ref "T6") (pin "2") (pinfunction "S_2") (pintype "passive"))
      (node (ref "T7") (pin "2") (pinfunction "S_2") (pintype "passive"))
      (node (ref "T8") (pin "2") (pinfunction "S_2") (pintype "passive"))
      (node (ref "T9") (pin "2") (pinfunction "S_2") (pintype "passive"))
      (node (ref "TEMP_SENS") (pin "4") (pinfunction "GND_4") (pintype "power_in"))
      (node (ref "TEMP_SENS") (pin "5") (pinfunction "A2_5") (pintype "bidirectional"))
      (node (ref "TEMP_SENS") (pin "6") (pinfunction "A1_6") (pintype "bidirectional"))
      (node (ref "TEMP_SENS") (pin "7") (pinfunction "A0_7") (pintype "bidirectional"))
      (node (ref "U$1") (pin "21") (pinfunction "GND_21") (pintype "power_in"))
      (node (ref "U$1") (pin "3") (pinfunction "GND_3") (pintype "power_in"))
      (node (ref "U$1") (pin "5") (pinfunction "GND_5") (pintype "power_in"))
      (node (ref "U$14") (pin "10") (pinfunction "GND_10") (pintype "bidirectional"))
      (node (ref "U$14") (pin "19") (pinfunction "NOT(OE)_19") (pintype "bidirectional"))
      (node (ref "U$19") (pin "10") (pinfunction "GND_10") (pintype "bidirectional"))
      (node (ref "U$19") (pin "15") (pinfunction "ADR0_15") (pintype "bidirectional"))
      (node (ref "U$19") (pin "16") (pinfunction "ADR1_16") (pintype "bidirectional"))
      (node (ref "U$19") (pin "17") (pinfunction "ADR2_17") (pintype "bidirectional"))
    )
    (net (code "113") (name "Net-(5V_F-PadP$2)") (class "Default")
      (node (ref "5V_F") (pin "P$2") (pinfunction "P$2_P$2") (pintype "bidirectional"))
      (node (ref "5V_SUPPLY") (pin "OUT") (pinfunction "OUT_OUT") (pintype "bidirectional"))
      (node (ref "C18") (pin "1") (pinfunction "1_1") (pintype "passive"))
    )
    (net (code "114") (name "Net-(12V_F1-PadP$2)") (class "Default")
      (node (ref "12V_F1") (pin "P$2") (pinfunction "P$2_P$2") (pintype "bidirectional"))
      (node (ref "C39") (pin "1") (pinfunction "1_1") (pintype "passive"))
      (node (ref "L10") (pin "1") (pinfunction "1_1") (pintype "passive"))
    )
    (net (code "115") (name "Net-(BLUETOOTH-P$11PIO(5))") (class "Default")
      (node (ref "BLUETOOTH") (pin "P$11") (pinfunction "P$11PIO(5)_P$11") (pintype "bidirectional"))
      (node (ref "R_DATA") (pin "2") (pinfunction "2_2") (pintype "passive"))
    )
    (net (code "116") (name "Net-(CP1-PLUS)") (class "Default")
      (node (ref "CP1") (pin "POS") (pinfunction "PLUS_POS") (pintype "power_in"))
      (node (ref "CP2") (pin "POS") (pinfunction "PLUS_POS") (pintype "power_in"))
      (node (ref "D11") (pin "3") (pinfunction "C_3") (pintype "passive"))
      (node (ref "L10") (pin "2") (pinfunction "2_2") (pintype "passive"))
      (node (ref "L8") (pin "1") (pinfunction "1_1") (pintype "passive"))
    )
    (net (code "117") (name "Net-(D4-A)") (class "Default")
      (node (ref "D4") (pin "1") (pinfunction "A_1") (pintype "passive"))
      (node (ref "R_DATA") (pin "1") (pinfunction "1_1") (pintype "passive"))
    )
    (net (code "118") (name "Net-(D5-A)") (class "Default")
      (node (ref "D5") (pin "1") (pinfunction "A_1") (pintype "passive"))
      (node (ref "R_CNT") (pin "1") (pinfunction "1_1") (pintype "passive"))
    )
    (net (code "119") (name "Net-(D11-A)") (class "Default")
      (node (ref "D11") (pin "1") (pinfunction "A_1") (pintype "passive"))
      (node (ref "R_R_LED_12") (pin "2") (pinfunction "2_2") (pintype "passive"))
    )
    (net (code "120") (name "Net-(D12-A)") (class "Default")
      (node (ref "D12") (pin "1") (pinfunction "A_1") (pintype "passive"))
      (node (ref "IC4") (pin "67") (pinfunction "PJ4(PCINT13)_67") (pintype "bidirectional"))
    )
    (net (code "121") (name "Net-(D14-A)") (class "Default")
      (node (ref "D14") (pin "1") (pinfunction "A_1") (pintype "passive"))
      (node (ref "R_DEAKT_DAUER_P") (pin "2") (pinfunction "2_2") (pintype "passive"))
      (node (ref "R_DEAKT_DAUER_P2") (pin "1") (pinfunction "1_1") (pintype "passive"))
      (node (ref "T13") (pin "3") (pinfunction "D_3") (pintype "passive"))
    )
    (net (code "122") (name "Net-(D18-C)") (class "Default")
      (node (ref "D18") (pin "3") (pinfunction "C_3") (pintype "passive"))
      (node (ref "R_E1_1") (pin "1") (pinfunction "1_1") (pintype "passive"))
      (node (ref "R_HB3") (pin "2") (pinfunction "2_2") (pintype "passive"))
    )
    (net (code "123") (name "Net-(D_GPS_FIX-A)") (class "Default")
      (node (ref "D_GPS_FIX") (pin "1") (pinfunction "A_1") (pintype "passive"))
      (node (ref "R_GPS_LED") (pin "2") (pinfunction "2_2") (pintype "passive"))
    )
    (net (code "124") (name "Net-(D_GR_BLR-CATHODE)") (class "Default")
      (node (ref "D_GR_BLR") (pin "P$4") (pinfunction "CATHODE_P$4") (pintype "bidirectional"))
      (node (ref "R_BL_R") (pin "1") (pinfunction "1_1") (pintype "passive"))
    )
    (net (code "125") (name "Net-(D_GR_N-CATHODE)") (class "Default")
      (node (ref "D_GR_N") (pin "P$4") (pinfunction "CATHODE_P$4") (pintype "bidirectional"))
      (node (ref "R_N") (pin "1") (pinfunction "1_1") (pintype "passive"))
    )
    (net (code "126") (name "Net-(D_L0-A)") (class "Default")
      (node (ref "D_L0") (pin "1") (pinfunction "A_1") (pintype "passive"))
      (node (ref "R_L0") (pin "2") (pinfunction "2_2") (pintype "passive"))
    )
    (net (code "127") (name "Net-(D_L1-A)") (class "Default")
      (node (ref "D_L1") (pin "1") (pinfunction "A_1") (pintype "passive"))
      (node (ref "R_L1") (pin "2") (pinfunction "2_2") (pintype "passive"))
    )
    (net (code "128") (name "Net-(D_L2-A)") (class "Default")
      (node (ref "D_L2") (pin "1") (pinfunction "A_1") (pintype "passive"))
      (node (ref "R_L2") (pin "2") (pinfunction "2_2") (pintype "passive"))
    )
    (net (code "129") (name "Net-(D_PWR_LED-A)") (class "Default")
      (node (ref "D_PWR_LED") (pin "1") (pinfunction "A_1") (pintype "passive"))
      (node (ref "R_LED_5V") (pin "2") (pinfunction "2_2") (pintype "passive"))
    )
    (net (code "130") (name "Net-(GPS_BAT-+)") (class "Default")
      (node (ref "D15") (pin "A") (pinfunction "A_A") (pintype "passive"))
      (node (ref "GPS_BAT") (pin "PWR@1") (pinfunction "+_PWR@1") (pintype "power_in"))
    )
    (net (code "131") (name "Net-(GPS_D1-C)") (class "Default")
      (node (ref "GPS_D1") (pin "3") (pinfunction "C_3") (pintype "passive"))
      (node (ref "GPS_D2") (pin "1") (pinfunction "A_1") (pintype "passive"))
    )
    (net (code "132") (name "Net-(GPS_D2-C)") (class "Default")
      (node (ref "D15") (pin "C") (pinfunction "C_C") (pintype "passive"))
      (node (ref "GPS") (pin "VBACKUP") (pinfunction "VBACKUP_VBACKUP") (pintype "bidirectional"))
      (node (ref "GPS_C2") (pin "1") (pinfunction "1_1") (pintype "passive"))
      (node (ref "GPS_D2") (pin "3") (pinfunction "C_3") (pintype "passive"))
    )
    (net (code "133") (name "Net-(IC1C-I1)") (class "Default")
      (node (ref "IC1") (pin "9") (pinfunction "I1_9") (pintype "input"))
      (node (ref "R_E1_0") (pin "1") (pinfunction "1_1") (pintype "passive"))
      (node (ref "R_E1_1") (pin "2") (pinfunction "2_2") (pintype "passive"))
      (node (ref "R_E1_2") (pin "1") (pinfunction "1_1") (pintype "passive"))
      (node (ref "R_E1_3") (pin "2") (pinfunction "2_2") (pintype "passive"))
    )
    (net (code "134") (name "Net-(IC1C-O)") (class "Default")
      (node (ref "IC1") (pin "10") (pinfunction "O_10") (pintype "output"))
      (node (ref "R_E1_4") (pin "1") (pinfunction "1_1") (pintype "passive"))
    )
    (net (code "135") (name "Net-(IC1D-I0)") (class "Default")
      (node (ref "IC1") (pin "12") (pinfunction "I0_12") (pintype "input"))
      (node (ref "R_REED") (pin "2") (pinfunction "2_2") (pintype "passive"))
      (node (ref "R_REED_DOWN") (pin "1") (pinfunction "1_1") (pintype "passive"))
      (node (ref "R_REED_UP") (pin "2") (pinfunction "2_2") (pintype "passive"))
    )
    (net (code "136") (name "Net-(IC4-AREF)") (class "Default")
      (node (ref "C31") (pin "1") (pinfunction "1_1") (pintype "passive"))
      (node (ref "IC4") (pin "98") (pinfunction "AREF_98") (pintype "bidirectional"))
    )
    (net (code "137") (name "Net-(IC4-XTAL1)") (class "Default")
      (node (ref "16MHZ") (pin "1") (pinfunction "1_1") (pintype "passive"))
      (node (ref "C7") (pin "1") (pinfunction "1_1") (pintype "passive"))
      (node (ref "IC4") (pin "34") (pinfunction "XTAL1_34") (pintype "input"))
    )
    (net (code "138") (name "Net-(IC4-XTAL2)") (class "Default")
      (node (ref "16MHZ") (pin "2") (pinfunction "2_2") (pintype "passive"))
      (node (ref "C5") (pin "1") (pinfunction "1_1") (pintype "passive"))
      (node (ref "IC4") (pin "33") (pinfunction "XTAL2_33") (pintype "output"))
    )
    (net (code "139") (name "Net-(Q1-D)") (class "Default")
      (node (ref "Q1") (pin "3") (pinfunction "D_3") (pintype "passive"))
      (node (ref "RGB_7") (pin "1+") (pinfunction "R_+_1+") (pintype "bidirectional"))
      (node (ref "RGB_7") (pin "2+") (pinfunction "G_+_2+") (pintype "bidirectional"))
      (node (ref "RGB_7") (pin "3+") (pinfunction "B_+_3+") (pintype "bidirectional"))
    )
    (net (code "140") (name "Net-(Q1-G)") (class "Default")
      (node (ref "Q1") (pin "1") (pinfunction "G_1") (pintype "passive"))
      (node (ref "U$19") (pin "1") (pinfunction "B0_1") (pintype "bidirectional"))
    )
    (net (code "141") (name "Net-(Q2-D)") (class "Default")
      (node (ref "Q2") (pin "3") (pinfunction "D_3") (pintype "passive"))
      (node (ref "RGB_6") (pin "1+") (pinfunction "R_+_1+") (pintype "bidirectional"))
      (node (ref "RGB_6") (pin "2+") (pinfunction "G_+_2+") (pintype "bidirectional"))
      (node (ref "RGB_6") (pin "3+") (pinfunction "B_+_3+") (pintype "bidirectional"))
    )
    (net (code "142") (name "Net-(Q2-G)") (class "Default")
      (node (ref "Q2") (pin "1") (pinfunction "G_1") (pintype "passive"))
      (node (ref "U$19") (pin "2") (pinfunction "B1_2") (pintype "bidirectional"))
    )
    (net (code "143") (name "Net-(Q3-D)") (class "Default")
      (node (ref "Q3") (pin "3") (pinfunction "D_3") (pintype "passive"))
      (node (ref "RGB_5") (pin "1+") (pinfunction "R_+_1+") (pintype "bidirectional"))
      (node (ref "RGB_5") (pin "2+") (pinfunction "G_+_2+") (pintype "bidirectional"))
      (node (ref "RGB_5") (pin "3+") (pinfunction "B_+_3+") (pintype "bidirectional"))
    )
    (net (code "144") (name "Net-(Q3-G)") (class "Default")
      (node (ref "Q3") (pin "1") (pinfunction "G_1") (pintype "passive"))
      (node (ref "U$19") (pin "3") (pinfunction "B2_3") (pintype "bidirectional"))
    )
    (net (code "145") (name "Net-(Q4-D)") (class "Default")
      (node (ref "Q4") (pin "3") (pinfunction "D_3") (pintype "passive"))
      (node (ref "RGB_4") (pin "1+") (pinfunction "R_+_1+") (pintype "bidirectional"))
      (node (ref "RGB_4") (pin "2+") (pinfunction "G_+_2+") (pintype "bidirectional"))
      (node (ref "RGB_4") (pin "3+") (pinfunction "B_+_3+") (pintype "bidirectional"))
    )
    (net (code "146") (name "Net-(Q4-G)") (class "Default")
      (node (ref "Q4") (pin "1") (pinfunction "G_1") (pintype "passive"))
      (node (ref "U$19") (pin "4") (pinfunction "B3_4") (pintype "bidirectional"))
    )
    (net (code "147") (name "Net-(Q5-D)") (class "Default")
      (node (ref "Q5") (pin "3") (pinfunction "D_3") (pintype "passive"))
      (node (ref "RGB_3") (pin "1+") (pinfunction "R_+_1+") (pintype "bidirectional"))
      (node (ref "RGB_3") (pin "2+") (pinfunction "G_+_2+") (pintype "bidirectional"))
      (node (ref "RGB_3") (pin "3+") (pinfunction "B_+_3+") (pintype "bidirectional"))
    )
    (net (code "148") (name "Net-(Q5-G)") (class "Default")
      (node (ref "Q5") (pin "1") (pinfunction "G_1") (pintype "passive"))
      (node (ref "U$19") (pin "5") (pinfunction "B4_5") (pintype "bidirectional"))
    )
    (net (code "149") (name "Net-(Q6-D)") (class "Default")
      (node (ref "Q6") (pin "3") (pinfunction "D_3") (pintype "passive"))
      (node (ref "RGB_2") (pin "1+") (pinfunction "R_+_1+") (pintype "bidirectional"))
      (node (ref "RGB_2") (pin "2+") (pinfunction "G_+_2+") (pintype "bidirectional"))
      (node (ref "RGB_2") (pin "3+") (pinfunction "B_+_3+") (pintype "bidirectional"))
    )
    (net (code "150") (name "Net-(Q6-G)") (class "Default")
      (node (ref "Q6") (pin "1") (pinfunction "G_1") (pintype "passive"))
      (node (ref "U$19") (pin "6") (pinfunction "B5_6") (pintype "bidirectional"))
    )
    (net (code "151") (name "Net-(Q7-D)") (class "Default")
      (node (ref "Q7") (pin "3") (pinfunction "D_3") (pintype "passive"))
      (node (ref "RGB_9") (pin "1+") (pinfunction "R_+_1+") (pintype "bidirectional"))
      (node (ref "RGB_9") (pin "2+") (pinfunction "G_+_2+") (pintype "bidirectional"))
      (node (ref "RGB_9") (pin "3+") (pinfunction "B_+_3+") (pintype "bidirectional"))
    )
    (net (code "152") (name "Net-(Q7-G)") (class "Default")
      (node (ref "Q7") (pin "1") (pinfunction "G_1") (pintype "passive"))
      (node (ref "U$19") (pin "7") (pinfunction "B6_7") (pintype "bidirectional"))
    )
    (net (code "153") (name "Net-(Q8-D)") (class "Default")
      (node (ref "Q8") (pin "3") (pinfunction "D_3") (pintype "passive"))
      (node (ref "RGB_8") (pin "1+") (pinfunction "R_+_1+") (pintype "bidirectional"))
      (node (ref "RGB_8") (pin "2+") (pinfunction "G_+_2+") (pintype "bidirectional"))
      (node (ref "RGB_8") (pin "3+") (pinfunction "B_+_3+") (pintype "bidirectional"))
    )
    (net (code "154") (name "Net-(Q8-G)") (class "Default")
      (node (ref "Q8") (pin "1") (pinfunction "G_1") (pintype "passive"))
      (node (ref "U$19") (pin "8") (pinfunction "B7_8") (pintype "bidirectional"))
    )
    (net (code "155") (name "Net-(Q9-D)") (class "Default")
      (node (ref "Q9") (pin "3") (pinfunction "D_3") (pintype "passive"))
      (node (ref "RGB_1") (pin "1+") (pinfunction "R_+_1+") (pintype "bidirectional"))
      (node (ref "RGB_1") (pin "2+") (pinfunction "G_+_2+") (pintype "bidirectional"))
      (node (ref "RGB_1") (pin "3+") (pinfunction "B_+_3+") (pintype "bidirectional"))
    )
    (net (code "156") (name "Net-(Q9-G)") (class "Default")
      (node (ref "Q9") (pin "1") (pinfunction "G_1") (pintype "passive"))
      (node (ref "U$19") (pin "21") (pinfunction "A0_21") (pintype "bidirectional"))
    )
    (net (code "157") (name "Net-(Q10-D)") (class "Default")
      (node (ref "Q10") (pin "3") (pinfunction "D_3") (pintype "passive"))
      (node (ref "RGB_10") (pin "1+") (pinfunction "R_+_1+") (pintype "bidirectional"))
      (node (ref "RGB_10") (pin "2+") (pinfunction "G_+_2+") (pintype "bidirectional"))
      (node (ref "RGB_10") (pin "3+") (pinfunction "B_+_3+") (pintype "bidirectional"))
    )
    (net (code "158") (name "Net-(Q10-G)") (class "Default")
      (node (ref "Q10") (pin "1") (pinfunction "G_1") (pintype "passive"))
      (node (ref "U$19") (pin "22") (pinfunction "A1_22") (pintype "bidirectional"))
    )
    (net (code "159") (name "Net-(Q11-D)") (class "Default")
      (node (ref "Q11") (pin "3") (pinfunction "D_3") (pintype "passive"))
      (node (ref "RGB_11") (pin "1+") (pinfunction "R_+_1+") (pintype "bidirectional"))
      (node (ref "RGB_11") (pin "2+") (pinfunction "G_+_2+") (pintype "bidirectional"))
      (node (ref "RGB_11") (pin "3+") (pinfunction "B_+_3+") (pintype "bidirectional"))
    )
    (net (code "160") (name "Net-(Q11-G)") (class "Default")
      (node (ref "Q11") (pin "1") (pinfunction "G_1") (pintype "passive"))
      (node (ref "U$19") (pin "23") (pinfunction "A2_23") (pintype "bidirectional"))
    )
    (net (code "161") (name "Net-(RGB_1-B_-)") (class "Default")
      (node (ref "RGB_1") (pin "3-") (pinfunction "B_-_3-") (pintype "bidirectional"))
      (node (ref "R_B_LED_11") (pin "1") (pinfunction "1_1") (pintype "passive"))
    )
    (net (code "162") (name "Net-(RGB_1-G_-)") (class "Default")
      (node (ref "RGB_1") (pin "2-") (pinfunction "G_-_2-") (pintype "bidirectional"))
      (node (ref "R_G_LED_11") (pin "1") (pinfunction "1_1") (pintype "passive"))
    )
    (net (code "163") (name "Net-(RGB_1-R_-)") (class "Default")
      (node (ref "RGB_1") (pin "1-") (pinfunction "R_-_1-") (pintype "bidirectional"))
      (node (ref "R_R_LED_11") (pin "1") (pinfunction "1_1") (pintype "passive"))
    )
    (net (code "164") (name "Net-(RGB_2-B_-)") (class "Default")
      (node (ref "RGB_2") (pin "3-") (pinfunction "B_-_3-") (pintype "bidirectional"))
      (node (ref "R_B_LED_1") (pin "1") (pinfunction "1_1") (pintype "passive"))
    )
    (net (code "165") (name "Net-(RGB_2-G_-)") (class "Default")
      (node (ref "RGB_2") (pin "2-") (pinfunction "G_-_2-") (pintype "bidirectional"))
      (node (ref "R_G_LED_1") (pin "1") (pinfunction "1_1") (pintype "passive"))
    )
    (net (code "166") (name "Net-(RGB_2-R_-)") (class "Default")
      (node (ref "RGB_2") (pin "1-") (pinfunction "R_-_1-") (pintype "bidirectional"))
      (node (ref "R_R_LED_1") (pin "1") (pinfunction "1_1") (pintype "passive"))
    )
    (net (code "167") (name "Net-(RGB_3-B_-)") (class "Default")
      (node (ref "RGB_3") (pin "3-") (pinfunction "B_-_3-") (pintype "bidirectional"))
      (node (ref "R_B_LED_2") (pin "1") (pinfunction "1_1") (pintype "passive"))
    )
    (net (code "168") (name "Net-(RGB_3-G_-)") (class "Default")
      (node (ref "RGB_3") (pin "2-") (pinfunction "G_-_2-") (pintype "bidirectional"))
      (node (ref "R_G_LED_2") (pin "1") (pinfunction "1_1") (pintype "passive"))
    )
    (net (code "169") (name "Net-(RGB_3-R_-)") (class "Default")
      (node (ref "RGB_3") (pin "1-") (pinfunction "R_-_1-") (pintype "bidirectional"))
      (node (ref "R_R_LED_2") (pin "1") (pinfunction "1_1") (pintype "passive"))
    )
    (net (code "170") (name "Net-(RGB_4-B_-)") (class "Default")
      (node (ref "RGB_4") (pin "3-") (pinfunction "B_-_3-") (pintype "bidirectional"))
      (node (ref "R_B_LED_3") (pin "1") (pinfunction "1_1") (pintype "passive"))
    )
    (net (code "171") (name "Net-(RGB_4-G_-)") (class "Default")
      (node (ref "RGB_4") (pin "2-") (pinfunction "G_-_2-") (pintype "bidirectional"))
      (node (ref "R_G_LED_3") (pin "1") (pinfunction "1_1") (pintype "passive"))
    )
    (net (code "172") (name "Net-(RGB_4-R_-)") (class "Default")
      (node (ref "RGB_4") (pin "1-") (pinfunction "R_-_1-") (pintype "bidirectional"))
      (node (ref "R_R_LED_3") (pin "1") (pinfunction "1_1") (pintype "passive"))
    )
    (net (code "173") (name "Net-(RGB_5-B_-)") (class "Default")
      (node (ref "RGB_5") (pin "3-") (pinfunction "B_-_3-") (pintype "bidirectional"))
      (node (ref "R_B_LED_4") (pin "1") (pinfunction "1_1") (pintype "passive"))
    )
    (net (code "174") (name "Net-(RGB_5-G_-)") (class "Default")
      (node (ref "RGB_5") (pin "2-") (pinfunction "G_-_2-") (pintype "bidirectional"))
      (node (ref "R_G_LED_4") (pin "1") (pinfunction "1_1") (pintype "passive"))
    )
    (net (code "175") (name "Net-(RGB_5-R_-)") (class "Default")
      (node (ref "RGB_5") (pin "1-") (pinfunction "R_-_1-") (pintype "bidirectional"))
      (node (ref "R_R_LED_4") (pin "1") (pinfunction "1_1") (pintype "passive"))
    )
    (net (code "176") (name "Net-(RGB_6-B_-)") (class "Default")
      (node (ref "RGB_6") (pin "3-") (pinfunction "B_-_3-") (pintype "bidirectional"))
      (node (ref "R_B_LED_5") (pin "1") (pinfunction "1_1") (pintype "passive"))
    )
    (net (code "177") (name "Net-(RGB_6-G_-)") (class "Default")
      (node (ref "RGB_6") (pin "2-") (pinfunction "G_-_2-") (pintype "bidirectional"))
      (node (ref "R_G_LED_5") (pin "1") (pinfunction "1_1") (pintype "passive"))
    )
    (net (code "178") (name "Net-(RGB_6-R_-)") (class "Default")
      (node (ref "RGB_6") (pin "1-") (pinfunction "R_-_1-") (pintype "bidirectional"))
      (node (ref "R_R_LED_5") (pin "1") (pinfunction "1_1") (pintype "passive"))
    )
    (net (code "179") (name "Net-(RGB_7-B_-)") (class "Default")
      (node (ref "RGB_7") (pin "3-") (pinfunction "B_-_3-") (pintype "bidirectional"))
      (node (ref "R_B_LED_6") (pin "1") (pinfunction "1_1") (pintype "passive"))
    )
    (net (code "180") (name "Net-(RGB_7-G_-)") (class "Default")
      (node (ref "RGB_7") (pin "2-") (pinfunction "G_-_2-") (pintype "bidirectional"))
      (node (ref "R_G_LED_6") (pin "1") (pinfunction "1_1") (pintype "passive"))
    )
    (net (code "181") (name "Net-(RGB_7-R_-)") (class "Default")
      (node (ref "RGB_7") (pin "1-") (pinfunction "R_-_1-") (pintype "bidirectional"))
      (node (ref "R_R_LED_6") (pin "1") (pinfunction "1_1") (pintype "passive"))
    )
    (net (code "182") (name "Net-(RGB_8-B_-)") (class "Default")
      (node (ref "RGB_8") (pin "3-") (pinfunction "B_-_3-") (pintype "bidirectional"))
      (node (ref "R_B_LED_10") (pin "1") (pinfunction "1_1") (pintype "passive"))
    )
    (net (code "183") (name "Net-(RGB_8-G_-)") (class "Default")
      (node (ref "RGB_8") (pin "2-") (pinfunction "G_-_2-") (pintype "bidirectional"))
      (node (ref "R_G_LED_10") (pin "1") (pinfunction "1_1") (pintype "passive"))
    )
    (net (code "184") (name "Net-(RGB_8-R_-)") (class "Default")
      (node (ref "RGB_8") (pin "1-") (pinfunction "R_-_1-") (pintype "bidirectional"))
      (node (ref "R_R_LED_10") (pin "1") (pinfunction "1_1") (pintype "passive"))
    )
    (net (code "185") (name "Net-(RGB_9-B_-)") (class "Default")
      (node (ref "RGB_9") (pin "3-") (pinfunction "B_-_3-") (pintype "bidirectional"))
      (node (ref "R_B_LED_9") (pin "1") (pinfunction "1_1") (pintype "passive"))
    )
    (net (code "186") (name "Net-(RGB_9-G_-)") (class "Default")
      (node (ref "RGB_9") (pin "2-") (pinfunction "G_-_2-") (pintype "bidirectional"))
      (node (ref "R_G_LED_9") (pin "1") (pinfunction "1_1") (pintype "passive"))
    )
    (net (code "187") (name "Net-(RGB_9-R_-)") (class "Default")
      (node (ref "RGB_9") (pin "1-") (pinfunction "R_-_1-") (pintype "bidirectional"))
      (node (ref "R_R_LED_9") (pin "1") (pinfunction "1_1") (pintype "passive"))
    )
    (net (code "188") (name "Net-(RGB_10-B_-)") (class "Default")
      (node (ref "RGB_10") (pin "3-") (pinfunction "B_-_3-") (pintype "bidirectional"))
      (node (ref "R_B_LED_8") (pin "1") (pinfunction "1_1") (pintype "passive"))
    )
    (net (code "189") (name "Net-(RGB_10-G_-)") (class "Default")
      (node (ref "RGB_10") (pin "2-") (pinfunction "G_-_2-") (pintype "bidirectional"))
      (node (ref "R_G_LED_8") (pin "1") (pinfunction "1_1") (pintype "passive"))
    )
    (net (code "190") (name "Net-(RGB_10-R_-)") (class "Default")
      (node (ref "RGB_10") (pin "1-") (pinfunction "R_-_1-") (pintype "bidirectional"))
      (node (ref "R_R_LED_8") (pin "1") (pinfunction "1_1") (pintype "passive"))
    )
    (net (code "191") (name "Net-(RGB_11-B_-)") (class "Default")
      (node (ref "RGB_11") (pin "3-") (pinfunction "B_-_3-") (pintype "bidirectional"))
      (node (ref "R_B_LED_7") (pin "1") (pinfunction "1_1") (pintype "passive"))
    )
    (net (code "192") (name "Net-(RGB_11-G_-)") (class "Default")
      (node (ref "RGB_11") (pin "2-") (pinfunction "G_-_2-") (pintype "bidirectional"))
      (node (ref "R_G_LED_7") (pin "1") (pinfunction "1_1") (pintype "passive"))
    )
    (net (code "193") (name "Net-(RGB_11-R_-)") (class "Default")
      (node (ref "RGB_11") (pin "1-") (pinfunction "R_-_1-") (pintype "bidirectional"))
      (node (ref "R_R_LED_7") (pin "1") (pinfunction "1_1") (pintype "passive"))
    )
    (net (code "194") (name "Net-(R_GR_BL_L-CATHODE)") (class "Default")
      (node (ref "R_BL_L") (pin "1") (pinfunction "1_1") (pintype "passive"))
      (node (ref "R_GR_BL_L") (pin "P$4") (pinfunction "CATHODE_P$4") (pintype "bidirectional"))
    )
    (net (code "195") (name "Net-(SPEEDOSTECKER-DAUER_VIN)") (class "Default")
      (node (ref "R_DEAKT_DAUER_P") (pin "1") (pinfunction "1_1") (pintype "passive"))
      (node (ref "SPEEDOSTECKER") (pin "P$14") (pinfunction "DAUER_VIN_P$14") (pintype "bidirectional"))
      (node (ref "T_P_BRIDGE") (pin "2") (pinfunction "S_2") (pintype "passive"))
    )
    (net (code "196") (name "Net-(SPEEDOSTECKER-EX_IN_OUT_A2)") (class "Default")
      (node (ref "R_E2_1") (pin "1") (pinfunction "1_1") (pintype "passive"))
      (node (ref "SPEEDOSTECKER") (pin "P$16") (pinfunction "EX_IN_OUT_A2_P$16") (pintype "bidirectional"))
    )
    (net (code "197") (name "Net-(SPEEDOSTECKER-EX_IN_OUT_D1)") (class "Default")
      (node (ref "R_HB3") (pin "1") (pinfunction "1_1") (pintype "passive"))
      (node (ref "SPEEDOSTECKER") (pin "P$13") (pinfunction "EX_IN_OUT_D1_P$13") (pintype "bidirectional"))
    )
    (net (code "198") (name "Net-(SPEEDOSTECKER-MC_COI)") (class "Default")
      (node (ref "R_HB4") (pin "1") (pinfunction "1_1") (pintype "passive"))
      (node (ref "SPEEDOSTECKER") (pin "P$7") (pinfunction "MC_COI_P$7") (pintype "output"))
    )
    (net (code "199") (name "Net-(SPEEDOSTECKER-OIL_TEMP)") (class "Default")
      (node (ref "R_OIL_OV") (pin "1") (pinfunction "1_1") (pintype "passive"))
      (node (ref "R_OIL_UP") (pin "1") (pinfunction "1_1") (pintype "passive"))
      (node (ref "SPEEDOSTECKER") (pin "P$2") (pinfunction "OIL_TEMP_P$2") (pintype "input"))
    )
    (net (code "200") (name "Net-(SPEEDOSTECKER-WATER_TEMP)") (class "Default")
      (node (ref "R_OIL_OV1") (pin "1") (pinfunction "1_1") (pintype "passive"))
      (node (ref "R_WATER_UP") (pin "2") (pinfunction "2_2") (pintype "passive"))
      (node (ref "SPEEDOSTECKER") (pin "P$12") (pinfunction "WATER_TEMP_P$12") (pintype "input"))
    )
    (net (code "201") (name "Net-(T1-D)") (class "Default")
      (node (ref "R_B_LED_1") (pin "2") (pinfunction "2_2") (pintype "passive"))
      (node (ref "R_B_LED_10") (pin "2") (pinfunction "2_2") (pintype "passive"))
      (node (ref "R_B_LED_11") (pin "2") (pinfunction "2_2") (pintype "passive"))
      (node (ref "R_B_LED_2") (pin "2") (pinfunction "2_2") (pintype "passive"))
      (node (ref "R_B_LED_3") (pin "2") (pinfunction "2_2") (pintype "passive"))
      (node (ref "R_B_LED_4") (pin "2") (pinfunction "2_2") (pintype "passive"))
      (node (ref "R_B_LED_5") (pin "2") (pinfunction "2_2") (pintype "passive"))
      (node (ref "R_B_LED_6") (pin "2") (pinfunction "2_2") (pintype "passive"))
      (node (ref "R_B_LED_7") (pin "2") (pinfunction "2_2") (pintype "passive"))
      (node (ref "R_B_LED_8") (pin "2") (pinfunction "2_2") (pintype "passive"))
      (node (ref "R_B_LED_9") (pin "2") (pinfunction "2_2") (pintype "passive"))
      (node (ref "T1") (pin "3") (pinfunction "D_3") (pintype "passive"))
    )
    (net (code "202") (name "Net-(T2-D)") (class "Default")
      (node (ref "R_G_LED_1") (pin "2") (pinfunction "2_2") (pintype "passive"))
      (node (ref "R_G_LED_10") (pin "2") (pinfunction "2_2") (pintype "passive"))
      (node (ref "R_G_LED_11") (pin "2") (pinfunction "2_2") (pintype "passive"))
      (node (ref "R_G_LED_2") (pin "2") (pinfunction "2_2") (pintype "passive"))
      (node (ref "R_G_LED_3") (pin "2") (pinfunction "2_2") (pintype "passive"))
      (node (ref "R_G_LED_4") (pin "2") (pinfunction "2_2") (pintype "passive"))
      (node (ref "R_G_LED_5") (pin "2") (pinfunction "2_2") (pintype "passive"))
      (node (ref "R_G_LED_6") (pin "2") (pinfunction "2_2") (pintype "passive"))
      (node (ref "R_G_LED_7") (pin "2") (pinfunction "2_2") (pintype "passive"))
      (node (ref "R_G_LED_8") (pin "2") (pinfunction "2_2") (pintype "passive"))
      (node (ref "R_G_LED_9") (pin "2") (pinfunction "2_2") (pintype "passive"))
      (node (ref "T2") (pin "3") (pinfunction "D_3") (pintype "passive"))
    )
    (net (code "203") (name "Net-(T5-D)") (class "Default")
      (node (ref "R_GPS_LED") (pin "1") (pinfunction "1_1") (pintype "passive"))
      (node (ref "T5") (pin "3") (pinfunction "D_3") (pintype "bidirectional"))
    )
    (net (code "204") (name "Net-(T5-G)") (class "Default")
      (node (ref "GPS") (pin "3D-FIX") (pinfunction "3D-FIX_3D-FIX") (pintype "bidirectional"))
      (node (ref "T5") (pin "1") (pinfunction "G_1") (pintype "input"))
    )
    (net (code "205") (name "Net-(T6-D)") (class "Default")
      (node (ref "R_N") (pin "2") (pinfunction "2_2") (pintype "passive"))
      (node (ref "T6") (pin "3") (pinfunction "D_3") (pintype "passive"))
    )
    (net (code "206") (name "Net-(T7-D)") (class "Default")
      (node (ref "R_HIGHB") (pin "2") (pinfunction "2_2") (pintype "passive"))
      (node (ref "T7") (pin "3") (pinfunction "D_3") (pintype "passive"))
    )
    (net (code "207") (name "Net-(T8-D)") (class "Default")
      (node (ref "R_OIL") (pin "2") (pinfunction "2_2") (pintype "passive"))
      (node (ref "T8") (pin "3") (pinfunction "D_3") (pintype "passive"))
    )
    (net (code "208") (name "Net-(T9-D)") (class "Default")
      (node (ref "R_BL_R") (pin "2") (pinfunction "2_2") (pintype "passive"))
      (node (ref "T9") (pin "3") (pinfunction "D_3") (pintype "passive"))
    )
    (net (code "209") (name "Net-(T10-D)") (class "Default")
      (node (ref "R_BL_L") (pin "2") (pinfunction "2_2") (pintype "passive"))
      (node (ref "T10") (pin "3") (pinfunction "D_3") (pintype "passive"))
    )
    (net (code "210") (name "Net-(T11-D)") (class "Default")
      (node (ref "R_R_LED_0") (pin "2") (pinfunction "2_2") (pintype "passive"))
      (node (ref "T11") (pin "3") (pinfunction "D_3") (pintype "passive"))
    )
    (net (code "211") (name "Net-(T12-D)") (class "Default")
      (node (ref "R_R_LED_1") (pin "2") (pinfunction "2_2") (pintype "passive"))
      (node (ref "R_R_LED_10") (pin "2") (pinfunction "2_2") (pintype "passive"))
      (node (ref "R_R_LED_11") (pin "2") (pinfunction "2_2") (pintype "passive"))
      (node (ref "R_R_LED_2") (pin "2") (pinfunction "2_2") (pintype "passive"))
      (node (ref "R_R_LED_3") (pin "2") (pinfunction "2_2") (pintype "passive"))
      (node (ref "R_R_LED_4") (pin "2") (pinfunction "2_2") (pintype "passive"))
      (node (ref "R_R_LED_5") (pin "2") (pinfunction "2_2") (pintype "passive"))
      (node (ref "R_R_LED_6") (pin "2") (pinfunction "2_2") (pintype "passive"))
      (node (ref "R_R_LED_7") (pin "2") (pinfunction "2_2") (pintype "passive"))
      (node (ref "R_R_LED_8") (pin "2") (pinfunction "2_2") (pintype "passive"))
      (node (ref "R_R_LED_9") (pin "2") (pinfunction "2_2") (pintype "passive"))
      (node (ref "T12") (pin "3") (pinfunction "D_3") (pintype "passive"))
      (node (ref "T3") (pin "3") (pinfunction "D_3") (pintype "passive"))
    )
    (net (code "212") (name "Net-(TEMP_SENS-OS)") (class "Default")
      (node (ref "R_TEMP_OS") (pin "1") (pinfunction "1_1") (pintype "passive"))
      (node (ref "TEMP_SENS") (pin "3") (pinfunction "OS_3") (pintype "bidirectional"))
    )
    (net (code "213") (name "Net-(TEMP_SENS-VDD)") (class "Default")
      (node (ref "C6") (pin "1") (pinfunction "1_1") (pintype "passive"))
      (node (ref "R_DELAY") (pin "1") (pinfunction "1_1") (pintype "passive"))
      (node (ref "TEMP_SENS") (pin "8") (pinfunction "VDD_8") (pintype "power_in"))
    )
    (net (code "214") (name "Net-(T_P_BRIDGE-D)") (class "Default")
      (node (ref "D_VERPOL1") (pin "A") (pinfunction "A_A") (pintype "passive"))
      (node (ref "T_P_BRIDGE") (pin "3") (pinfunction "D_3") (pintype "passive"))
    )
    (net (code "215") (name "Net-(T_P_BRIDGE-G)") (class "Default")
      (node (ref "R_DEAKT_DAUER_P2") (pin "2") (pinfunction "2_2") (pintype "passive"))
      (node (ref "T_P_BRIDGE") (pin "1") (pinfunction "G_1") (pintype "passive"))
    )
    (net (code "216") (name "Net-(U$1-(PCINT6{slash}XTAL1{slash}TOSC1)PB6)") (class "Default")
      (node (ref "16MHZ1") (pin "1") (pinfunction "1_1") (pintype "passive"))
      (node (ref "C_QUA_5") (pin "2") (pinfunction "2_2") (pintype "passive"))
      (node (ref "U$1") (pin "7") (pinfunction "(PCINT6/XTAL1/TOSC1)PB6_7") (pintype "bidirectional"))
    )
    (net (code "217") (name "Net-(U$1-(PCINT7{slash}XTAL2{slash}TOSC2)PB7)") (class "Default")
      (node (ref "16MHZ1") (pin "2") (pinfunction "2_2") (pintype "passive"))
      (node (ref "C_QUA_4") (pin "2") (pinfunction "2_2") (pintype "passive"))
      (node (ref "U$1") (pin "8") (pinfunction "(PCINT7/XTAL2/TOSC2)PB7_8") (pintype "bidirectional"))
    )
    (net (code "218") (name "Net-(U$1-(PCINT21{slash}OC0B{slash}T1)PD5)") (class "Default")
      (node (ref "R_L0") (pin "1") (pinfunction "1_1") (pintype "passive"))
      (node (ref "U$1") (pin "9") (pinfunction "(PCINT21/OC0B/T1)PD5_9") (pintype "bidirectional"))
    )
    (net (code "219") (name "Net-(U$1-(PCINT22{slash}OC0A{slash}AIN0)PD6)") (class "Default")
      (node (ref "R_L1") (pin "1") (pinfunction "1_1") (pintype "passive"))
      (node (ref "U$1") (pin "10") (pinfunction "(PCINT22/OC0A/AIN0)PD6_10") (pintype "bidirectional"))
    )
    (net (code "220") (name "Net-(U$1-(PCINT23{slash}AIN1)PD7)") (class "Default")
      (node (ref "R_L2") (pin "1") (pinfunction "1_1") (pintype "passive"))
      (node (ref "U$1") (pin "11") (pinfunction "(PCINT23/AIN1)PD7_11") (pintype "bidirectional"))
    )
    (net (code "221") (name "Net-(U$1-AREF)") (class "Default")
      (node (ref "AT8_REF") (pin "2") (pinfunction "2_2") (pintype "passive"))
      (node (ref "C1") (pin "1") (pinfunction "1_1") (pintype "passive"))
      (node (ref "U$1") (pin "18") (pinfunction "AVCC_18") (pintype "power_in"))
      (node (ref "U$1") (pin "20") (pinfunction "AREF_20") (pintype "passive"))
    )
    (net (code "222") (name "Net-(U$3-CATHODE)") (class "Default")
      (node (ref "R_HIGHB") (pin "1") (pinfunction "1_1") (pintype "passive"))
      (node (ref "U$3") (pin "P$4") (pinfunction "CATHODE_P$4") (pintype "bidirectional"))
    )
    (net (code "223") (name "Net-(U$11-CATHODE)") (class "Default")
      (node (ref "R_OIL") (pin "1") (pinfunction "1_1") (pintype "passive"))
      (node (ref "U$11") (pin "P$4") (pinfunction "CATHODE_P$4") (pintype "bidirectional"))
    )
    (net (code "224") (name "Net-(U$22-CATHODE)") (class "Default")
      (node (ref "R_R_LED_0") (pin "1") (pinfunction "1_1") (pintype "passive"))
      (node (ref "U$22") (pin "P$4") (pinfunction "CATHODE_P$4") (pintype "bidirectional"))
    )
    (net (code "225") (name "VDD") (class "Default")
      (node (ref "5V_F") (pin "P$1") (pinfunction "P$1_P$1") (pintype "bidirectional"))
      (node (ref "C32") (pin "1") (pinfunction "1_1") (pintype "passive"))
      (node (ref "C33") (pin "1") (pinfunction "1_1") (pintype "passive"))
      (node (ref "C34") (pin "1") (pinfunction "1_1") (pintype "passive"))
      (node (ref "D9") (pin "A") (pinfunction "A_A") (pintype "passive"))
      (node (ref "D_GR_BLR") (pin "P$1") (pinfunction "ANODE_P$1") (pintype "bidirectional"))
      (node (ref "D_GR_BLR") (pin "P$2") (pinfunction "ANODE_P$2") (pintype "bidirectional"))
      (node (ref "D_GR_BLR") (pin "P$3") (pinfunction "ANODE_P$3") (pintype "bidirectional"))
      (node (ref "D_GR_N") (pin "P$1") (pinfunction "ANODE_P$1") (pintype "bidirectional"))
      (node (ref "D_GR_N") (pin "P$2") (pinfunction "ANODE_P$2") (pintype "bidirectional"))
      (node (ref "D_GR_N") (pin "P$3") (pinfunction "ANODE_P$3") (pintype "bidirectional"))
      (node (ref "IC1") (pin "1") (pinfunction "I0_1") (pintype "input"))
      (node (ref "IC1") (pin "13") (pinfunction "I1_13") (pintype "input"))
      (node (ref "IC1") (pin "14") (pinfunction "VDD_14") (pintype "power_in"))
      (node (ref "IC1") (pin "8") (pinfunction "I0_8") (pintype "input"))
      (node (ref "IC4") (pin "10") (pinfunction "VCC_10") (pintype "power_in"))
      (node (ref "IC4") (pin "100") (pinfunction "AVCC_100") (pintype "power_in"))
      (node (ref "IC4") (pin "31") (pinfunction "VCC1_31") (pintype "power_in"))
      (node (ref "IC4") (pin "61") (pinfunction "VCC2_61") (pintype "power_in"))
      (node (ref "IC4") (pin "80") (pinfunction "VCC3_80") (pintype "power_in"))
      (node (ref "JP1") (pin "5") (pinfunction "5_5") (pintype "passive"))
      (node (ref "PE") (pin "2") (pinfunction "2_2") (pintype "passive"))
      (node (ref "PWR") (pin "2") (pinfunction "2_2") (pintype "passive"))
      (node (ref "PWR1") (pin "2") (pinfunction "2_2") (pintype "passive"))
      (node (ref "Q1") (pin "2") (pinfunction "S_2") (pintype "passive"))
      (node (ref "Q10") (pin "2") (pinfunction "S_2") (pintype "passive"))
      (node (ref "Q11") (pin "2") (pinfunction "S_2") (pintype "passive"))
      (node (ref "Q2") (pin "2") (pinfunction "S_2") (pintype "passive"))
      (node (ref "Q3") (pin "2") (pinfunction "S_2") (pintype "passive"))
      (node (ref "Q4") (pin "2") (pinfunction "S_2") (pintype "passive"))
      (node (ref "Q5") (pin "2") (pinfunction "S_2") (pintype "passive"))
      (node (ref "Q6") (pin "2") (pinfunction "S_2") (pintype "passive"))
      (node (ref "Q7") (pin "2") (pinfunction "S_2") (pintype "passive"))
      (node (ref "Q8") (pin "2") (pinfunction "S_2") (pintype "passive"))
      (node (ref "Q9") (pin "2") (pinfunction "S_2") (pintype "passive"))
      (node (ref "R_DELAY") (pin "2") (pinfunction "2_2") (pintype "passive"))
      (node (ref "R_E1_0") (pin "2") (pinfunction "2_2") (pintype "passive"))
      (node (ref "R_GR_BL_L") (pin "P$1") (pinfunction "ANODE_P$1") (pintype "bidirectional"))
      (node (ref "R_GR_BL_L") (pin "P$2") (pinfunction "ANODE_P$2") (pintype "bidirectional"))
      (node (ref "R_GR_BL_L") (pin "P$3") (pinfunction "ANODE_P$3") (pintype "bidirectional"))
      (node (ref "R_L3") (pin "1") (pinfunction "1_1") (pintype "passive"))
      (node (ref "R_LED_5V") (pin "1") (pinfunction "1_1") (pintype "passive"))
      (node (ref "R_OIL_UP") (pin "2") (pinfunction "2_2") (pintype "passive"))
      (node (ref "R_REED_UP") (pin "1") (pinfunction "1_1") (pintype "passive"))
      (node (ref "R_RES_UP") (pin "2") (pinfunction "2_2") (pintype "passive"))
      (node (ref "R_SCL_UP") (pin "1") (pinfunction "1_1") (pintype "passive"))
      (node (ref "R_SDA_UP") (pin "1") (pinfunction "1_1") (pintype "passive"))
      (node (ref "R_TEMP_OS") (pin "2") (pinfunction "2_2") (pintype "passive"))
      (node (ref "R_WATER_UP") (pin "1") (pinfunction "1_1") (pintype "passive"))
      (node (ref "U$11") (pin "P$1") (pinfunction "ANODE_P$1") (pintype "bidirectional"))
      (node (ref "U$11") (pin "P$2") (pinfunction "ANODE_P$2") (pintype "bidirectional"))
      (node (ref "U$11") (pin "P$3") (pinfunction "ANODE_P$3") (pintype "bidirectional"))
      (node (ref "U$19") (pin "18") (pinfunction "NOT(RESET)_18") (pintype "bidirectional"))
      (node (ref "U$19") (pin "9") (pinfunction "VCC_9") (pintype "bidirectional"))
      (node (ref "U$22") (pin "P$1") (pinfunction "ANODE_P$1") (pintype "bidirectional"))
      (node (ref "U$22") (pin "P$2") (pinfunction "ANODE_P$2") (pintype "bidirectional"))
      (node (ref "U$22") (pin "P$3") (pinfunction "ANODE_P$3") (pintype "bidirectional"))
      (node (ref "U$3") (pin "P$1") (pinfunction "ANODE_P$1") (pintype "bidirectional"))
      (node (ref "U$3") (pin "P$2") (pinfunction "ANODE_P$2") (pintype "bidirectional"))
      (node (ref "U$3") (pin "P$3") (pinfunction "ANODE_P$3") (pintype "bidirectional"))
    )
    (net (code "226") (name "unconnected-(BLUETOOTH-P$3_AIO(0)-PadP$3)") (class "Default")
      (node (ref "BLUETOOTH") (pin "P$3") (pinfunction "P$3_AIO(0)_P$3") (pintype "bidirectional"))
    )
    (net (code "227") (name "unconnected-(BLUETOOTH-P$4_AIO(1)-PadP$4)") (class "Default")
      (node (ref "BLUETOOTH") (pin "P$4") (pinfunction "P$4_AIO(1)_P$4") (pintype "bidirectional"))
    )
    (net (code "228") (name "unconnected-(BLUETOOTH-P$5_PIO(0)-PadP$5)") (class "Default")
      (node (ref "BLUETOOTH") (pin "P$5") (pinfunction "P$5_PIO(0)_P$5") (pintype "bidirectional"))
    )
    (net (code "229") (name "unconnected-(BLUETOOTH-P$6_PIO(1)-PadP$6)") (class "Default")
      (node (ref "BLUETOOTH") (pin "P$6") (pinfunction "P$6_PIO(1)_P$6") (pintype "bidirectional"))
    )
    (net (code "230") (name "unconnected-(BLUETOOTH-P$7_PIO(2)-PadP$7)") (class "Default")
      (node (ref "BLUETOOTH") (pin "P$7") (pinfunction "P$7_PIO(2)_P$7") (pintype "bidirectional"))
    )
    (net (code "231") (name "unconnected-(BLUETOOTH-P$8_PIO(3)-PadP$8)") (class "Default")
      (node (ref "BLUETOOTH") (pin "P$8") (pinfunction "P$8_PIO(3)_P$8") (pintype "bidirectional"))
    )
    (net (code "232") (name "unconnected-(BLUETOOTH-P$9_PIO(4)-PadP$9)") (class "Default")
      (node (ref "BLUETOOTH") (pin "P$9") (pinfunction "P$9_PIO(4)_P$9") (pintype "bidirectional"))
    )
    (net (code "233") (name "unconnected-(BLUETOOTH-P$12_PIO(6)-PadP$12)") (class "Default")
      (node (ref "BLUETOOTH") (pin "P$12") (pinfunction "P$12_PIO(6)_P$12") (pintype "bidirectional"))
    )
    (net (code "234") (name "unconnected-(BLUETOOTH-P$14_PIO(8)-PadP$14)") (class "Default")
      (node (ref "BLUETOOTH") (pin "P$14") (pinfunction "P$14_PIO(8)_P$14") (pintype "bidirectional"))
    )
    (net (code "235") (name "unconnected-(BLUETOOTH-P$15_PIO(9)-PadP$15)") (class "Default")
      (node (ref "BLUETOOTH") (pin "P$15") (pinfunction "P$15_PIO(9)_P$15") (pintype "bidirectional"))
    )
    (net (code "236") (name "unconnected-(BLUETOOTH-P$16_RESET-PadP$16)") (class "Default")
      (node (ref "BLUETOOTH") (pin "P$16") (pinfunction "P$16_RESET_P$16") (pintype "input"))
    )
    (net (code "237") (name "unconnected-(BLUETOOTH-P$20_USB-DP-PadP$20)") (class "Default")
      (node (ref "BLUETOOTH") (pin "P$20") (pinfunction "P$20_USB-DP_P$20") (pintype "bidirectional"))
    )
    (net (code "238") (name "unconnected-(BLUETOOTH-P$21_USB-DN-PadP$21)") (class "Default")
      (node (ref "BLUETOOTH") (pin "P$21") (pinfunction "P$21_USB-DN_P$21") (pintype "bidirectional"))
    )
    (net (code "239") (name "unconnected-(BLUETOOTH-P$22_PCM-SYNC-PadP$22)") (class "Default")
      (node (ref "BLUETOOTH") (pin "P$22") (pinfunction "P$22_PCM-SYNC_P$22") (pintype "bidirectional"))
    )
    (net (code "240") (name "unconnected-(BLUETOOTH-P$23_PCM-IN-PadP$23)") (class "Default")
      (node (ref "BLUETOOTH") (pin "P$23") (pinfunction "P$23_PCM-IN_P$23") (pintype "input"))
    )
    (net (code "241") (name "unconnected-(BLUETOOTH-P$24_PCM-OUT-PadP$24)") (class "Default")
      (node (ref "BLUETOOTH") (pin "P$24") (pinfunction "P$24_PCM-OUT_P$24") (pintype "output"))
    )
    (net (code "242") (name "unconnected-(BLUETOOTH-P$25_PCM-CLK-PadP$25)") (class "Default")
      (node (ref "BLUETOOTH") (pin "P$25") (pinfunction "P$25_PCM-CLK_P$25") (pintype "bidirectional"))
    )
    (net (code "243") (name "unconnected-(BLUETOOTH-P$28_UART-RTS-PadP$28)") (class "Default")
      (node (ref "BLUETOOTH") (pin "P$28") (pinfunction "P$28_UART-RTS_P$28") (pintype "output"))
    )
    (net (code "244") (name "unconnected-(BLUETOOTH-P$30_UART-CTS-PadP$30)") (class "Default")
      (node (ref "BLUETOOTH") (pin "P$30") (pinfunction "P$30_UART-CTS_P$30") (pintype "input"))
    )
    (net (code "245") (name "unconnected-(BLUETOOTH-P$31_SPI-MOSI-PadP$31)") (class "Default")
      (node (ref "BLUETOOTH") (pin "P$31") (pinfunction "P$31_SPI-MOSI_P$31") (pintype "input"))
    )
    (net (code "246") (name "unconnected-(BLUETOOTH-P$32_SPI-CSB-PadP$32)") (class "Default")
      (node (ref "BLUETOOTH") (pin "P$32") (pinfunction "P$32_SPI-CSB_P$32") (pintype "input"))
    )
    (net (code "247") (name "unconnected-(BLUETOOTH-P$33_SPI-CLK-PadP$33)") (class "Default")
      (node (ref "BLUETOOTH") (pin "P$33") (pinfunction "P$33_SPI-CLK_P$33") (pintype "input"))
    )
    (net (code "248") (name "unconnected-(BLUETOOTH-P$34_SPI-MISO-PadP$34)") (class "Default")
      (node (ref "BLUETOOTH") (pin "P$34") (pinfunction "P$34_SPI-MISO_P$34") (pintype "output"))
    )
    (net (code "249") (name "unconnected-(BLUETOOTH-P$35_PIO(11)-PadP$35)") (class "Default")
      (node (ref "BLUETOOTH") (pin "P$35") (pinfunction "P$35_PIO(11)_P$35") (pintype "bidirectional"))
    )
    (net (code "250") (name "unconnected-(BLUETOOTH-P$36_PIO(10)-PadP$36)") (class "Default")
      (node (ref "BLUETOOTH") (pin "P$36") (pinfunction "P$36_PIO(10)_P$36") (pintype "bidirectional"))
    )
    (net (code "251") (name "unconnected-(GPS-DMINUS-PadD+)") (class "Default")
      (node (ref "GPS") (pin "D+") (pinfunction "DMINUS_D+") (pintype "bidirectional"))
    )
    (net (code "252") (name "unconnected-(GPS-DPLUS-PadD-)") (class "Default")
      (node (ref "GPS") (pin "D-") (pinfunction "DPLUS_D-") (pintype "bidirectional"))
    )
    (net (code "253") (name "unconnected-(IC4-(T1)PD6-Pad49)") (class "Default")
      (node (ref "IC4") (pin "49") (pinfunction "(T1)PD6_49") (pintype "bidirectional"))
    )
    (net (code "254") (name "unconnected-(IC4-(TOSC1)PG4-Pad29)") (class "Default")
      (node (ref "IC4") (pin "29") (pinfunction "(TOSC1)PG4_29") (pintype "bidirectional"))
    )
    (net (code "255") (name "unconnected-(IC4-(TOSC2)PG3-Pad28)") (class "Default")
      (node (ref "IC4") (pin "28") (pinfunction "(TOSC2)PG3_28") (pintype "bidirectional"))
    )
    (net (code "256") (name "unconnected-(IC4-(XCK0{slash}AIN0)PE2-Pad4)") (class "Default")
      (node (ref "IC4") (pin "4") (pinfunction "(XCK0/AIN0)PE2_4") (pintype "bidirectional"))
    )
    (net (code "257") (name "unconnected-(IC4-(XCK1)PD5-Pad48)") (class "Default")
      (node (ref "IC4") (pin "48") (pinfunction "(XCK1)PD5_48") (pintype "bidirectional"))
    )
    (net (code "258") (name "unconnected-(IC4-PH0(RXD2)-Pad12)") (class "Default")
      (node (ref "IC4") (pin "12") (pinfunction "PH0(RXD2)_12") (pintype "bidirectional"))
    )
    (net (code "259") (name "unconnected-(IC4-PH1(TXD2)-Pad13)") (class "Default")
      (node (ref "IC4") (pin "13") (pinfunction "PH1(TXD2)_13") (pintype "bidirectional"))
    )
    (net (code "260") (name "unconnected-(IC4-PH2(XCK2)-Pad14)") (class "Default")
      (node (ref "IC4") (pin "14") (pinfunction "PH2(XCK2)_14") (pintype "bidirectional"))
    )
    (net (code "261") (name "unconnected-(IC4-PH7(T4)-Pad27)") (class "Default")
      (node (ref "IC4") (pin "27") (pinfunction "PH7(T4)_27") (pintype "bidirectional"))
    )
    (net (code "262") (name "unconnected-(IC4-PJ2(XCK3{slash}PCINT11)-Pad65)") (class "Default")
      (node (ref "IC4") (pin "65") (pinfunction "PJ2(XCK3/PCINT11)_65") (pintype "bidirectional"))
    )
    (net (code "263") (name "unconnected-(IC4-PJ7-Pad79)") (class "Default")
      (node (ref "IC4") (pin "79") (pinfunction "PJ7_79") (pintype "bidirectional"))
    )
    (net (code "264") (name "unconnected-(NHD_2.7-NC-PadNC0)") (class "Default")
      (node (ref "NHD_2.7") (pin "NC0") (pinfunction "NC_NC0") (pintype "bidirectional"))
    )
    (net (code "265") (name "unconnected-(NHD_2.7-NC2-PadNC1)") (class "Default")
      (node (ref "NHD_2.7") (pin "NC1") (pinfunction "NC2_NC1") (pintype "bidirectional"))
    )
    (net (code "266") (name "unconnected-(NHD_2.7-NC3-PadNC2)") (class "Default")
      (node (ref "NHD_2.7") (pin "NC2") (pinfunction "NC3_NC2") (pintype "bidirectional"))
    )
    (net (code "267") (name "unconnected-(NHD_2.7-NC4-PadNC3)") (class "Default")
      (node (ref "NHD_2.7") (pin "NC3") (pinfunction "NC4_NC3") (pintype "bidirectional"))
    )
    (net (code "268") (name "unconnected-(R_E2_0-Pad1)") (class "Default")
      (node (ref "R_E2_0") (pin "1") (pinfunction "1_1") (pintype "passive"))
    )
    (net (code "269") (name "unconnected-(ST2-DAT1-Pad8)") (class "Default")
      (node (ref "ST2") (pin "8") (pinfunction "DAT1_8") (pintype "bidirectional"))
    )
    (net (code "270") (name "unconnected-(ST2-DAT2-Pad1)") (class "Default")
      (node (ref "ST2") (pin "1") (pinfunction "DAT2_1") (pintype "bidirectional"))
    )
    (net (code "271") (name "unconnected-(U$1-(ADC4{slash}PCINT12{slash}SDA)PC4-Pad27)") (class "Default")
      (node (ref "U$1") (pin "27") (pinfunction "(ADC4/PCINT12/SDA)PC4_27") (pintype "output"))
    )
    (net (code "272") (name "unconnected-(U$1-(PCINT0{slash}CLKO{slash}ICP1)PB0-Pad12)") (class "Default")
      (node (ref "U$1") (pin "12") (pinfunction "(PCINT0/CLKO/ICP1)PB0_12") (pintype "bidirectional"))
    )
    (net (code "273") (name "unconnected-(U$1-(PCINT1{slash}OC1A)PB1-Pad13)") (class "Default")
      (node (ref "U$1") (pin "13") (pinfunction "(PCINT1/OC1A)PB1_13") (pintype "bidirectional"))
    )
    (net (code "274") (name "unconnected-(U$1-(PCINT2{slash}~{SS}{slash}OC1B)PB2-Pad14)") (class "Default")
      (node (ref "U$1") (pin "14") (pinfunction "(PCINT2/~{SS}/OC1B)PB2_14") (pintype "bidirectional"))
    )
    (net (code "275") (name "unconnected-(U$1-ADC6-Pad19)") (class "Default")
      (node (ref "U$1") (pin "19") (pinfunction "ADC6_19") (pintype "bidirectional"))
    )
    (net (code "276") (name "unconnected-(U$1-ADC7-Pad22)") (class "Default")
      (node (ref "U$1") (pin "22") (pinfunction "ADC7_22") (pintype "bidirectional"))
    )
    (net (code "277") (name "unconnected-(U$14-A0-Pad2)") (class "Default")
      (node (ref "U$14") (pin "2") (pinfunction "A0_2") (pintype "bidirectional"))
    )
    (net (code "278") (name "unconnected-(U$14-A1-Pad3)") (class "Default")
      (node (ref "U$14") (pin "3") (pinfunction "A1_3") (pintype "bidirectional"))
    )
    (net (code "279") (name "unconnected-(U$14-A2-Pad4)") (class "Default")
      (node (ref "U$14") (pin "4") (pinfunction "A2_4") (pintype "bidirectional"))
    )
    (net (code "280") (name "unconnected-(U$14-A3-Pad5)") (class "Default")
      (node (ref "U$14") (pin "5") (pinfunction "A3_5") (pintype "bidirectional"))
    )
    (net (code "281") (name "unconnected-(U$14-A4-Pad6)") (class "Default")
      (node (ref "U$14") (pin "6") (pinfunction "A4_6") (pintype "bidirectional"))
    )
    (net (code "282") (name "unconnected-(U$14-B0-Pad18)") (class "Default")
      (node (ref "U$14") (pin "18") (pinfunction "B0_18") (pintype "bidirectional"))
    )
    (net (code "283") (name "unconnected-(U$14-B1-Pad17)") (class "Default")
      (node (ref "U$14") (pin "17") (pinfunction "B1_17") (pintype "bidirectional"))
    )
    (net (code "284") (name "unconnected-(U$14-B2-Pad16)") (class "Default")
      (node (ref "U$14") (pin "16") (pinfunction "B2_16") (pintype "bidirectional"))
    )
    (net (code "285") (name "unconnected-(U$14-B3-Pad15)") (class "Default")
      (node (ref "U$14") (pin "15") (pinfunction "B3_15") (pintype "bidirectional"))
    )
    (net (code "286") (name "unconnected-(U$14-B4-Pad14)") (class "Default")
      (node (ref "U$14") (pin "14") (pinfunction "B4_14") (pintype "bidirectional"))
    )
    (net (code "287") (name "unconnected-(U$19-INTA-Pad20)") (class "Default")
      (node (ref "U$19") (pin "20") (pinfunction "INTA_20") (pintype "bidirectional"))
    )
    (net (code "288") (name "unconnected-(U$19-INTB-Pad19)") (class "Default")
      (node (ref "U$19") (pin "19") (pinfunction "INTB_19") (pintype "bidirectional"))
    )
    (net (code "289") (name "unconnected-(U$19-NC1-Pad11)") (class "Default")
      (node (ref "U$19") (pin "11") (pinfunction "NC1_11") (pintype "bidirectional"))
    )
    (net (code "290") (name "unconnected-(U$19-NC2-Pad14)") (class "Default")
      (node (ref "U$19") (pin "14") (pinfunction "NC2_14") (pintype "bidirectional"))
    )
  )
)
